# Sheet_1_2024-04-25.net
KiCad netlist of a schematic drawn in Altium Designer
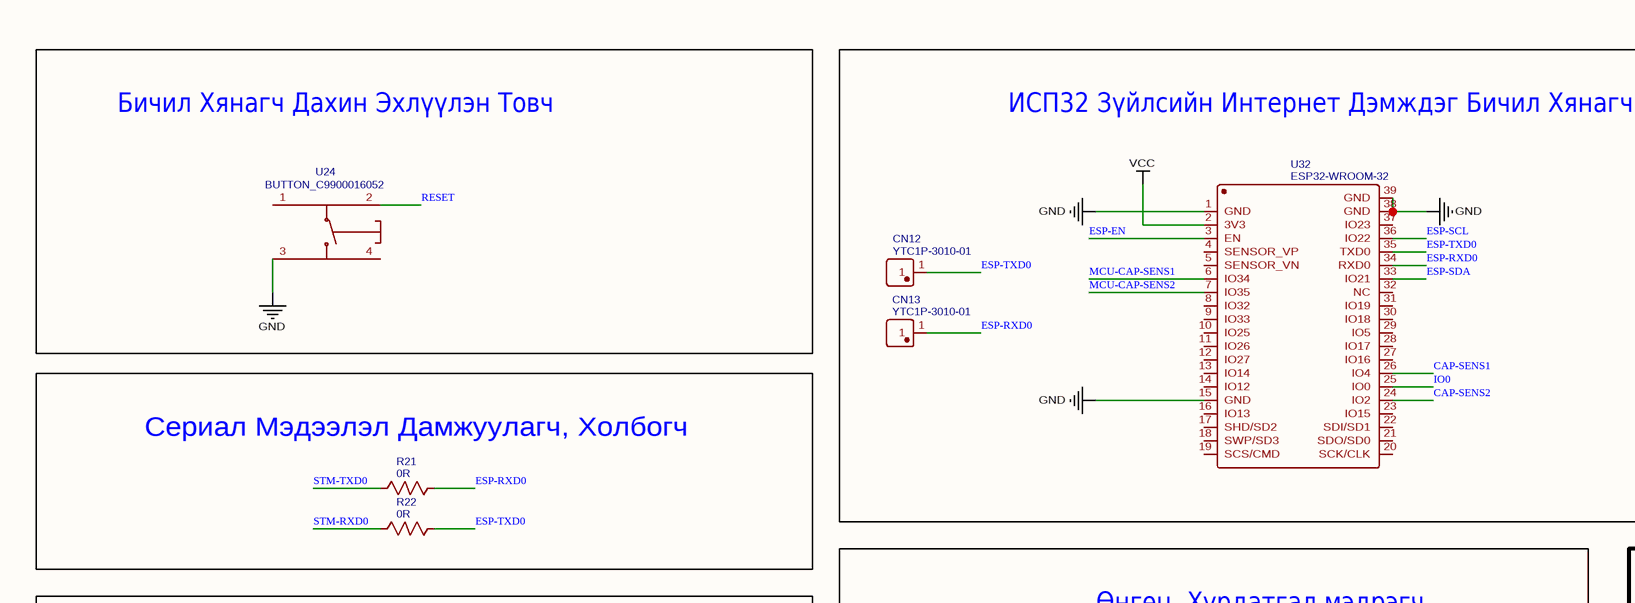
[diagram p0: Sheet_1_2024-04-25.schdoc, top left]
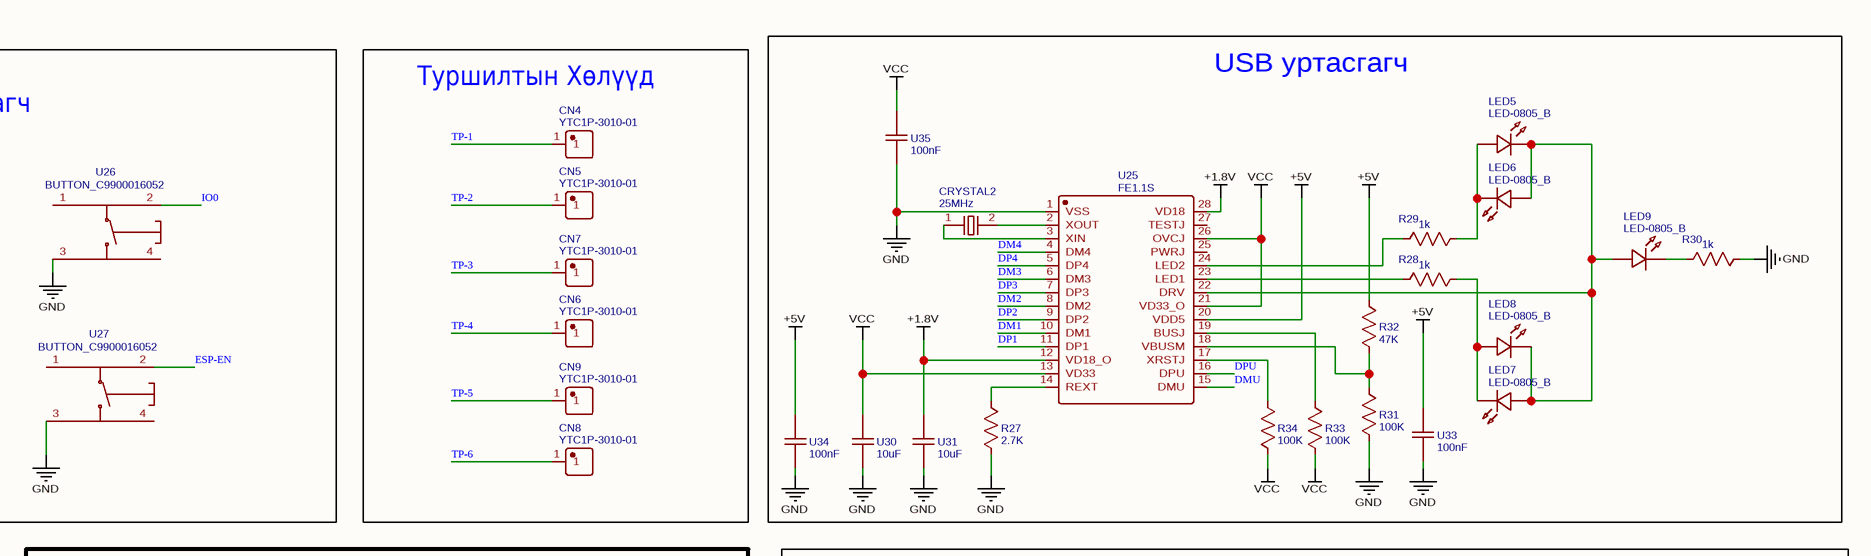
[diagram p1: Sheet_1_2024-04-25.schdoc, top right]
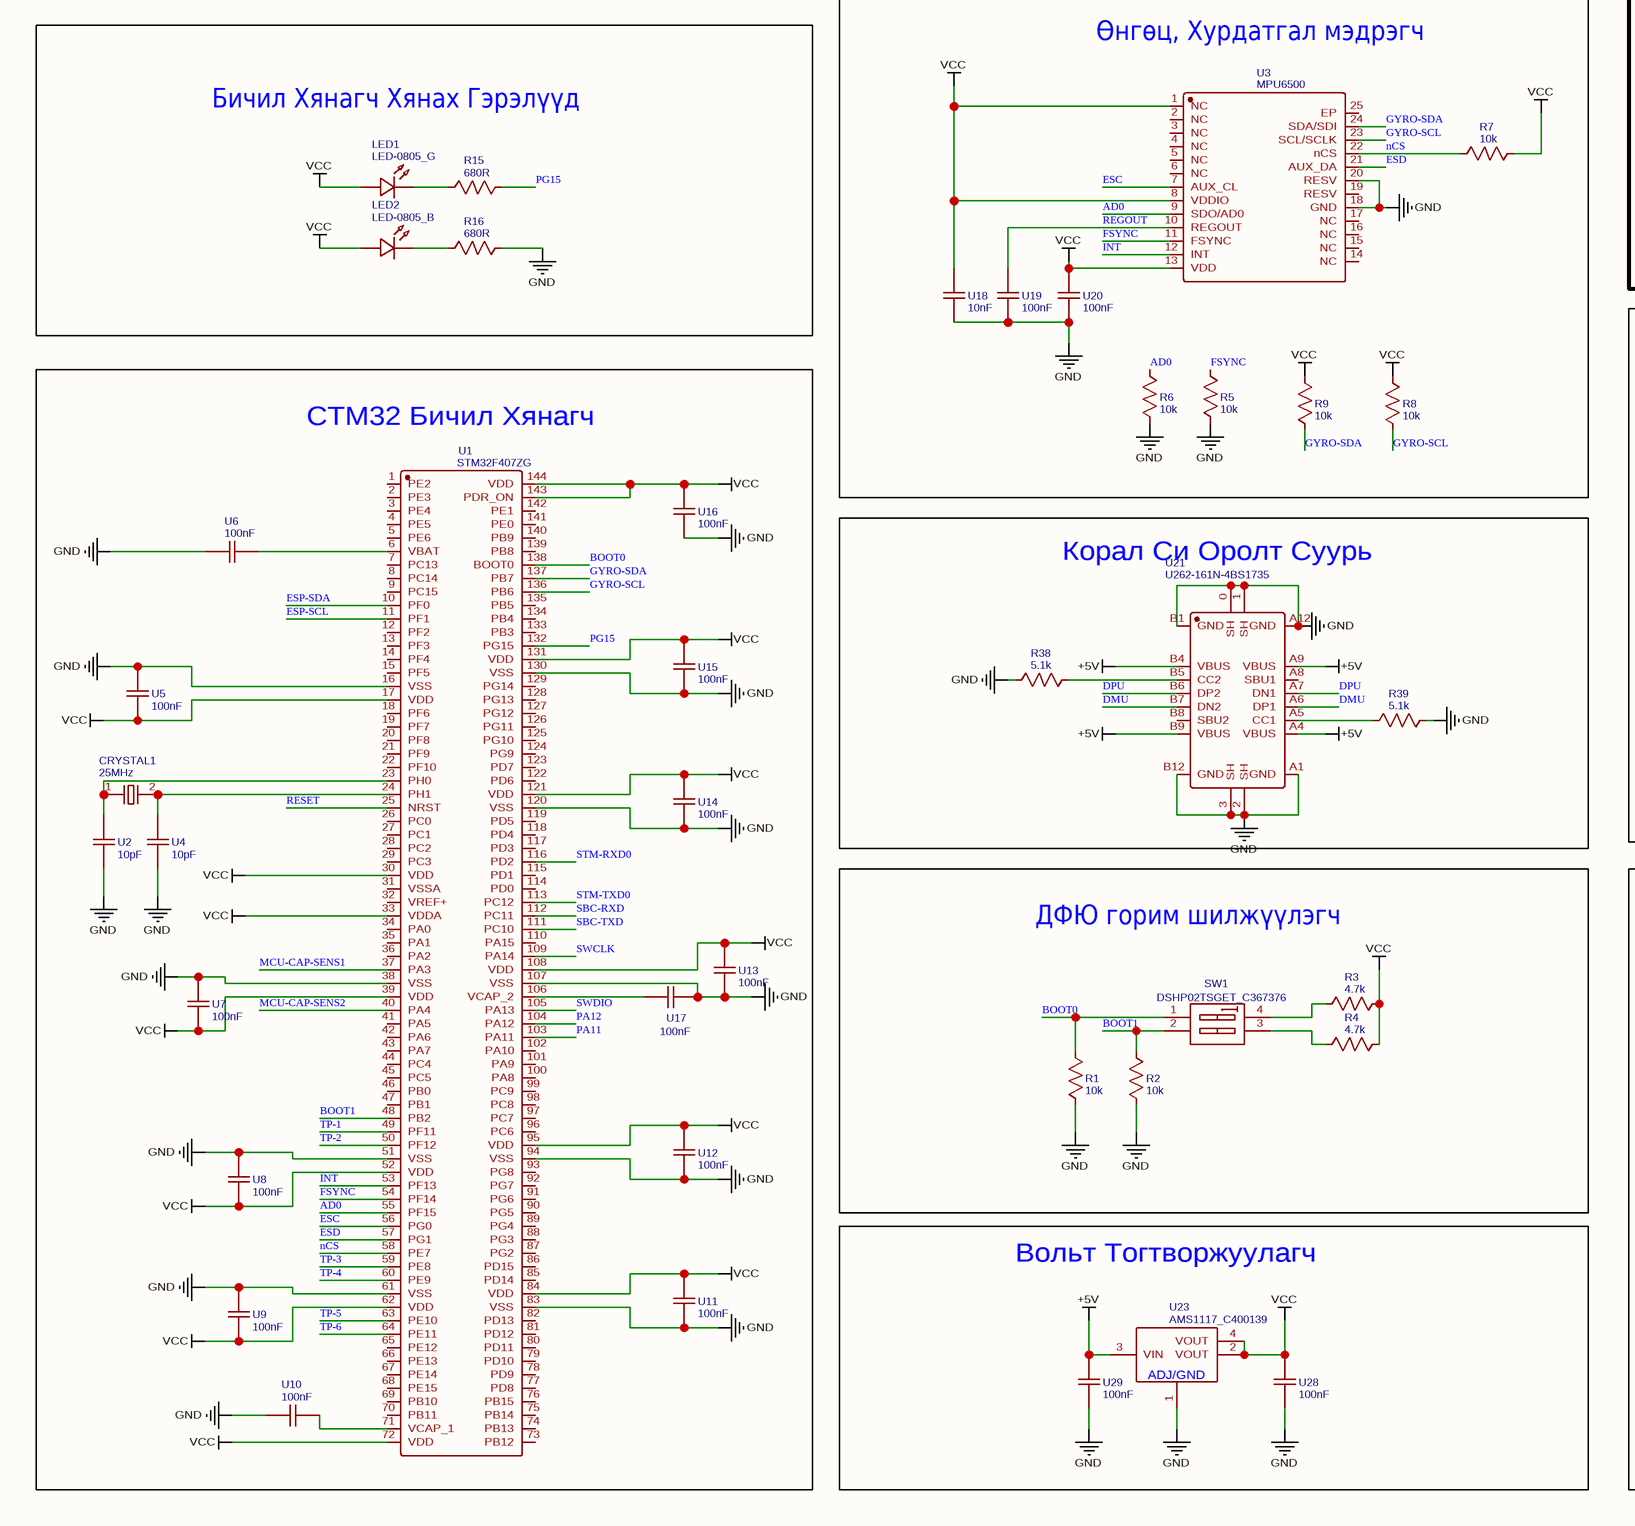
[diagram p2: Sheet_1_2024-04-25.schdoc, bottom left]
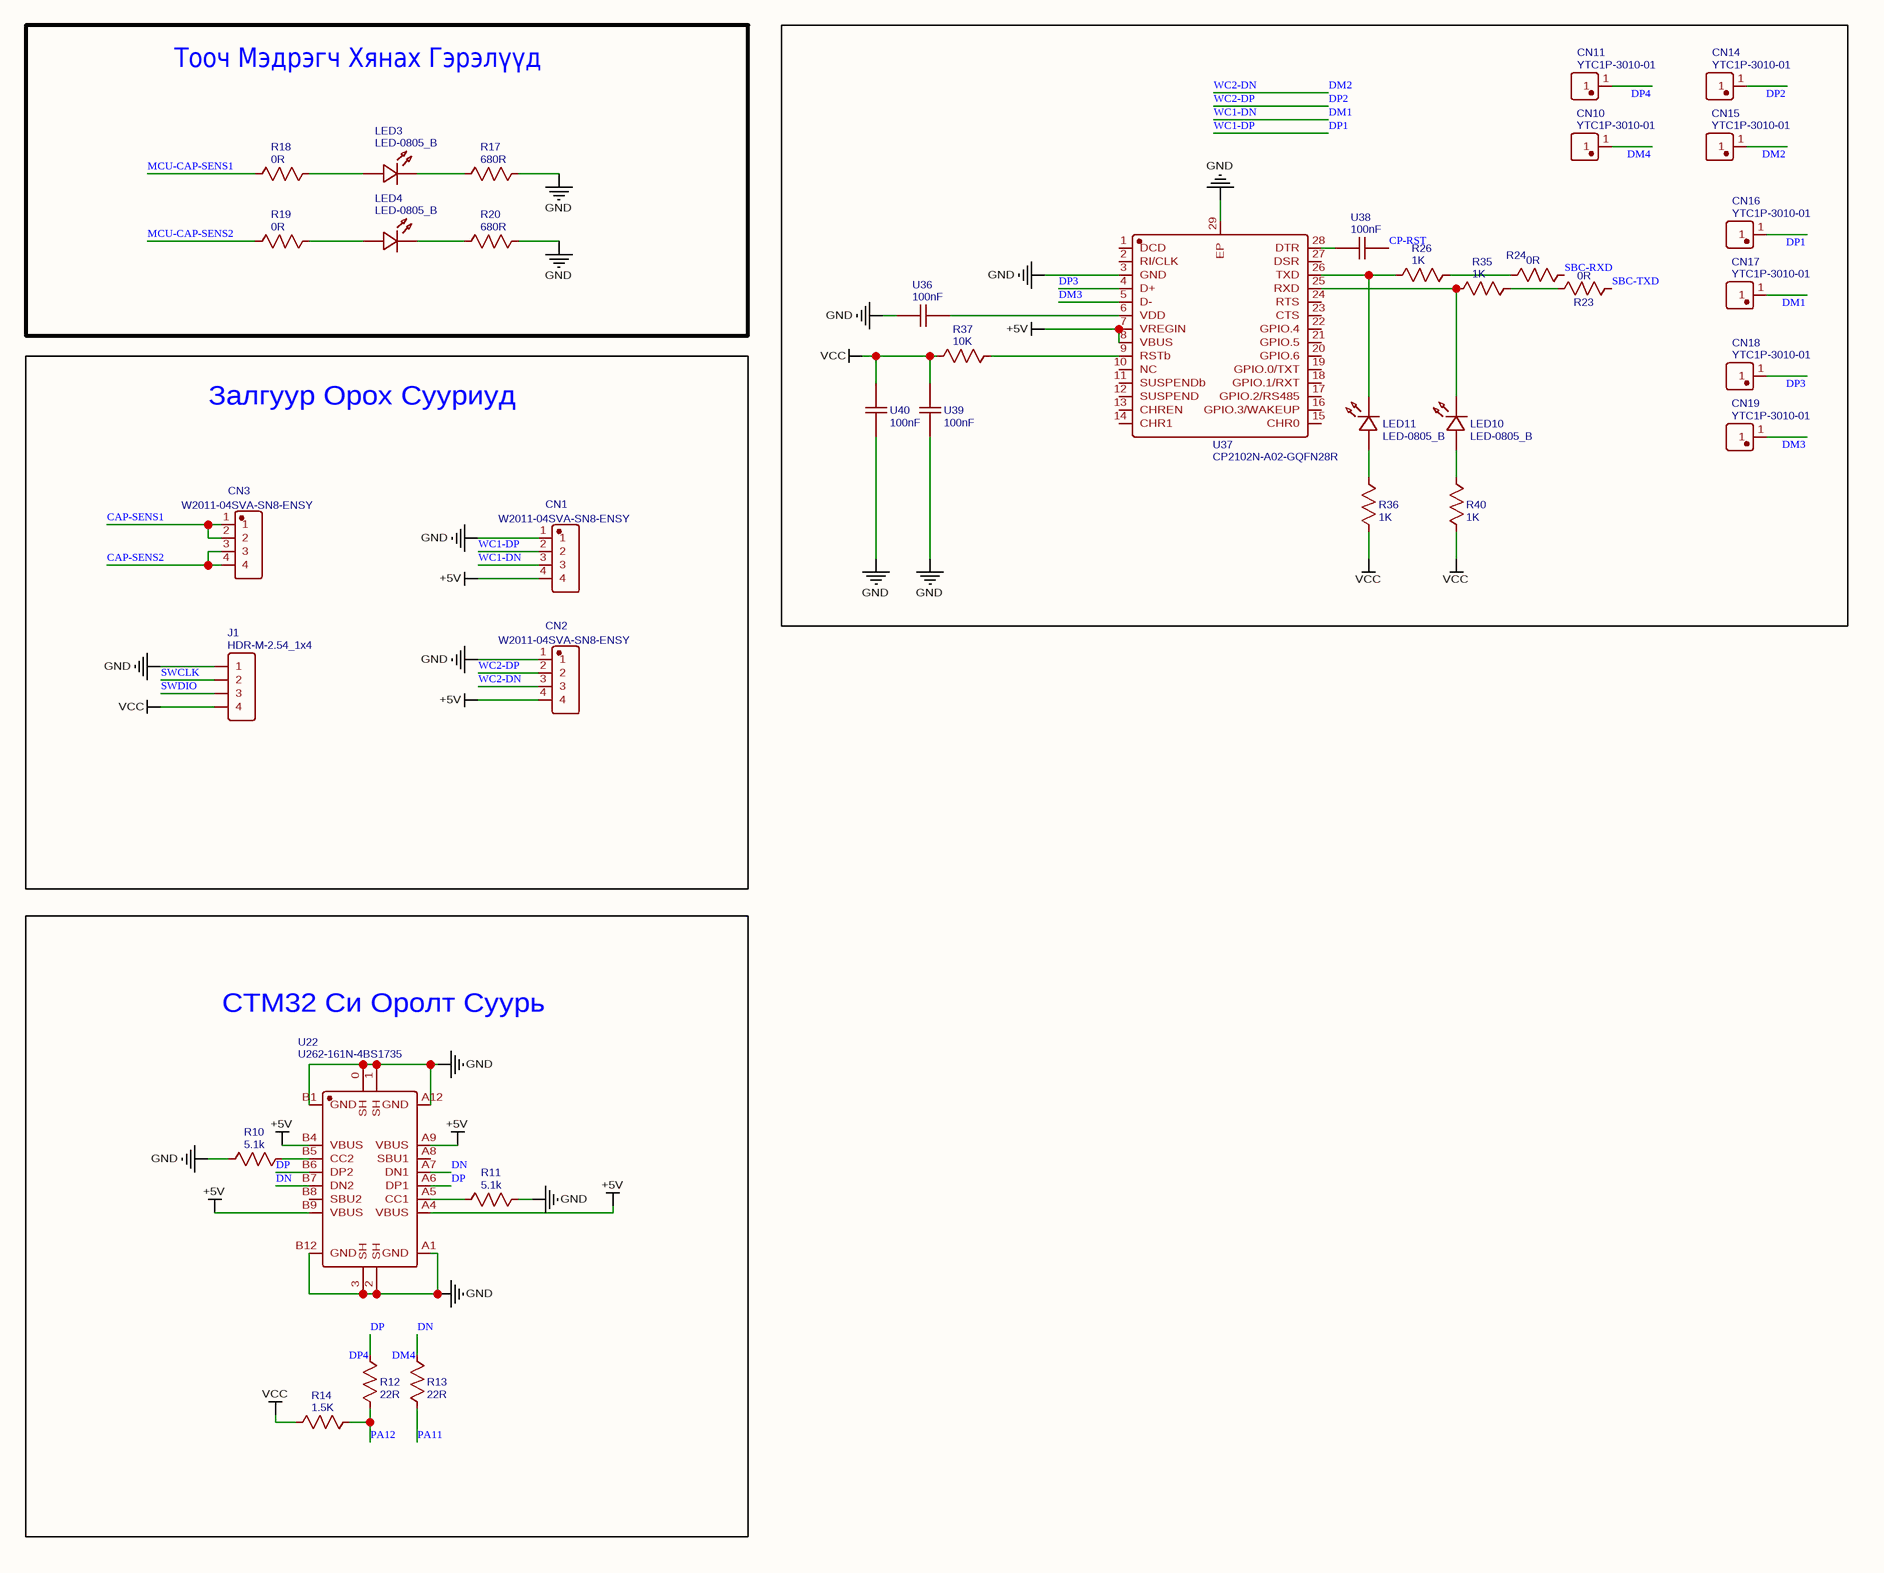
[diagram p3: Sheet_1_2024-04-25.schdoc, bottom right]

(export (version "E")
  (design (tool "Eeschema 10.0.6"))
  (components
    (comp (ref "CN1")
      (value "W2011-04SVA-SN8-ENSY")
      (fields (field (name "CONTRIBUTOR") "lcsc"))
      (libsource (lib "altium-import") (part "root_0_W2011-04SVA-SN8-ENSY_"))
    )
    (comp (ref "CN2")
      (value "W2011-04SVA-SN8-ENSY")
      (fields (field (name "CONTRIBUTOR") "lcsc"))
      (libsource (lib "altium-import") (part "root_0_W2011-04SVA-SN8-ENSY_"))
    )
    (comp (ref "CN3")
      (value "W2011-04SVA-SN8-ENSY")
      (fields (field (name "CONTRIBUTOR") "lcsc"))
      (libsource (lib "altium-import") (part "root_0_W2011-04SVA-SN8-ENSY_"))
    )
    (comp (ref "CN4")
      (value "YTC1P-3010-01")
      (fields (field (name "MANUFACTURER") "YIYUAN(怡远)") (field (name "CONTRIBUTOR") "lcsc"))
      (libsource (lib "altium-import") (part "root_0_YTC1P-3010-01_"))
    )
    (comp (ref "CN5")
      (value "YTC1P-3010-01")
      (fields (field (name "MANUFACTURER") "YIYUAN(怡远)") (field (name "CONTRIBUTOR") "lcsc"))
      (libsource (lib "altium-import") (part "root_0_YTC1P-3010-01_"))
    )
    (comp (ref "CN6")
      (value "YTC1P-3010-01")
      (fields (field (name "MANUFACTURER") "YIYUAN(怡远)") (field (name "CONTRIBUTOR") "lcsc"))
      (libsource (lib "altium-import") (part "root_0_YTC1P-3010-01_"))
    )
    (comp (ref "CN7")
      (value "YTC1P-3010-01")
      (fields (field (name "MANUFACTURER") "YIYUAN(怡远)") (field (name "CONTRIBUTOR") "lcsc"))
      (libsource (lib "altium-import") (part "root_0_YTC1P-3010-01_"))
    )
    (comp (ref "CN8")
      (value "YTC1P-3010-01")
      (fields (field (name "MANUFACTURER") "YIYUAN(怡远)") (field (name "CONTRIBUTOR") "lcsc"))
      (libsource (lib "altium-import") (part "root_0_YTC1P-3010-01_"))
    )
    (comp (ref "CN9")
      (value "YTC1P-3010-01")
      (fields (field (name "MANUFACTURER") "YIYUAN(怡远)") (field (name "CONTRIBUTOR") "lcsc"))
      (libsource (lib "altium-import") (part "root_0_YTC1P-3010-01_"))
    )
    (comp (ref "CN10")
      (value "YTC1P-3010-01")
      (fields (field (name "MANUFACTURER") "YIYUAN(怡远)") (field (name "CONTRIBUTOR") "lcsc"))
      (libsource (lib "altium-import") (part "root_2_YTC1P-3010-01_"))
    )
    (comp (ref "CN11")
      (value "YTC1P-3010-01")
      (fields (field (name "MANUFACTURER") "YIYUAN(怡远)") (field (name "CONTRIBUTOR") "lcsc"))
      (libsource (lib "altium-import") (part "root_2_YTC1P-3010-01_"))
    )
    (comp (ref "CN12")
      (value "YTC1P-3010-01")
      (fields (field (name "MANUFACTURER") "YIYUAN(怡远)") (field (name "CONTRIBUTOR") "lcsc"))
      (libsource (lib "altium-import") (part "root_2_YTC1P-3010-01_"))
    )
    (comp (ref "CN13")
      (value "YTC1P-3010-01")
      (fields (field (name "MANUFACTURER") "YIYUAN(怡远)") (field (name "CONTRIBUTOR") "lcsc"))
      (libsource (lib "altium-import") (part "root_2_YTC1P-3010-01_"))
    )
    (comp (ref "CN14")
      (value "YTC1P-3010-01")
      (fields (field (name "MANUFACTURER") "YIYUAN(怡远)") (field (name "CONTRIBUTOR") "lcsc"))
      (libsource (lib "altium-import") (part "root_2_YTC1P-3010-01_"))
    )
    (comp (ref "CN15")
      (value "YTC1P-3010-01")
      (fields (field (name "MANUFACTURER") "YIYUAN(怡远)") (field (name "CONTRIBUTOR") "lcsc"))
      (libsource (lib "altium-import") (part "root_2_YTC1P-3010-01_"))
    )
    (comp (ref "CN16")
      (value "YTC1P-3010-01")
      (fields (field (name "MANUFACTURER") "YIYUAN(怡远)") (field (name "CONTRIBUTOR") "lcsc"))
      (libsource (lib "altium-import") (part "root_2_YTC1P-3010-01_"))
    )
    (comp (ref "CN17")
      (value "YTC1P-3010-01")
      (fields (field (name "MANUFACTURER") "YIYUAN(怡远)") (field (name "CONTRIBUTOR") "lcsc"))
      (libsource (lib "altium-import") (part "root_2_YTC1P-3010-01_"))
    )
    (comp (ref "CN18")
      (value "YTC1P-3010-01")
      (fields (field (name "MANUFACTURER") "YIYUAN(怡远)") (field (name "CONTRIBUTOR") "lcsc"))
      (libsource (lib "altium-import") (part "root_2_YTC1P-3010-01_"))
    )
    (comp (ref "CN19")
      (value "YTC1P-3010-01")
      (fields (field (name "MANUFACTURER") "YIYUAN(怡远)") (field (name "CONTRIBUTOR") "lcsc"))
      (libsource (lib "altium-import") (part "root_2_YTC1P-3010-01_"))
    )
    (comp (ref "CRYSTAL1")
      (value "25MHz")
      (fields
        (field (name "MANUFACTURER") "HUAXIN(华昕)")
        (field (name "MANUFACTURER PART") "SD2012M00020001")
        (field (name "CONTRIBUTOR") "lcsc")
      )
      (libsource (lib "altium-import") (part "root_0_25MHz_"))
    )
    (comp (ref "CRYSTAL2")
      (value "25MHz")
      (fields
        (field (name "MANUFACTURER") "HUAXIN(华昕)")
        (field (name "MANUFACTURER PART") "SD2012M00020001")
        (field (name "CONTRIBUTOR") "lcsc")
      )
      (libsource (lib "altium-import") (part "root_0_25MHz_"))
    )
    (comp (ref "J1")
      (value "HDR-M-2.54_1x4")
      (fields (field (name "CONTRIBUTOR") "LCEDA_Lib"))
      (libsource (lib "altium-import") (part "root_0_HDR-M-2.54_1x4_"))
    )
    (comp (ref "LED1")
      (value "LED-0805_G")
      (fields
        (field (name "MANUFACTURER") "国星光电")
        (field (name "MANUFACTURER PART") "NCD0805G1")
        (field (name "CONTRIBUTOR") "LCEDA_Lib")
      )
      (libsource (lib "altium-import") (part "root_0_LED-0805_G_"))
    )
    (comp (ref "LED2")
      (value "LED-0805_B")
      (fields
        (field (name "MANUFACTURER") "方舟 ARKLED")
        (field (name "MANUFACTURER PART") "D-B080508B1-KS2")
        (field (name "CONTRIBUTOR") "LCEDA_Lib")
      )
      (libsource (lib "altium-import") (part "root_0_LED-0805_B_"))
    )
    (comp (ref "LED3")
      (value "LED-0805_B")
      (fields
        (field (name "MANUFACTURER") "方舟 ARKLED")
        (field (name "MANUFACTURER PART") "D-B080508B1-KS2")
        (field (name "CONTRIBUTOR") "LCEDA_Lib")
      )
      (libsource (lib "altium-import") (part "root_0_LED-0805_B_"))
    )
    (comp (ref "LED4")
      (value "LED-0805_B")
      (fields
        (field (name "MANUFACTURER") "方舟 ARKLED")
        (field (name "MANUFACTURER PART") "D-B080508B1-KS2")
        (field (name "CONTRIBUTOR") "LCEDA_Lib")
      )
      (libsource (lib "altium-import") (part "root_0_LED-0805_B_"))
    )
    (comp (ref "LED5")
      (value "LED-0805_B")
      (fields
        (field (name "MANUFACTURER") "方舟 ARKLED")
        (field (name "MANUFACTURER PART") "D-B080508B1-KS2")
        (field (name "CONTRIBUTOR") "LCEDA_Lib")
      )
      (libsource (lib "altium-import") (part "root_0_LED-0805_B_"))
    )
    (comp (ref "LED6")
      (value "LED-0805_B")
      (fields
        (field (name "MANUFACTURER") "方舟 ARKLED")
        (field (name "MANUFACTURER PART") "D-B080508B1-KS2")
        (field (name "CONTRIBUTOR") "LCEDA_Lib")
      )
      (libsource (lib "altium-import") (part "root_2_LED-0805_B_"))
    )
    (comp (ref "LED7")
      (value "LED-0805_B")
      (fields
        (field (name "MANUFACTURER") "方舟 ARKLED")
        (field (name "MANUFACTURER PART") "D-B080508B1-KS2")
        (field (name "CONTRIBUTOR") "LCEDA_Lib")
      )
      (libsource (lib "altium-import") (part "root_2_LED-0805_B_"))
    )
    (comp (ref "LED8")
      (value "LED-0805_B")
      (fields
        (field (name "MANUFACTURER") "方舟 ARKLED")
        (field (name "MANUFACTURER PART") "D-B080508B1-KS2")
        (field (name "CONTRIBUTOR") "LCEDA_Lib")
      )
      (libsource (lib "altium-import") (part "root_0_LED-0805_B_"))
    )
    (comp (ref "LED9")
      (value "LED-0805_B")
      (fields
        (field (name "MANUFACTURER") "方舟 ARKLED")
        (field (name "MANUFACTURER PART") "D-B080508B1-KS2")
        (field (name "CONTRIBUTOR") "LCEDA_Lib")
      )
      (libsource (lib "altium-import") (part "root_0_LED-0805_B_"))
    )
    (comp (ref "LED10")
      (value "LED-0805_B")
      (fields
        (field (name "MANUFACTURER") "方舟 ARKLED")
        (field (name "MANUFACTURER PART") "D-B080508B1-KS2")
        (field (name "CONTRIBUTOR") "LCEDA_Lib")
      )
      (libsource (lib "altium-import") (part "root_1_LED-0805_B_"))
    )
    (comp (ref "LED11")
      (value "LED-0805_B")
      (fields
        (field (name "MANUFACTURER") "方舟 ARKLED")
        (field (name "MANUFACTURER PART") "D-B080508B1-KS2")
        (field (name "CONTRIBUTOR") "LCEDA_Lib")
      )
      (libsource (lib "altium-import") (part "root_1_LED-0805_B_"))
    )
    (comp (ref "R1")
      (value "10k")
      (fields (field (name "CONTRIBUTOR") "LCEDA_Lib"))
      (libsource (lib "altium-import") (part "root_1_10k_"))
    )
    (comp (ref "R2")
      (value "10k")
      (fields (field (name "CONTRIBUTOR") "LCEDA_Lib"))
      (libsource (lib "altium-import") (part "root_1_10k_"))
    )
    (comp (ref "R3")
      (value "4.7k")
      (fields (field (name "CONTRIBUTOR") "LCEDA_Lib"))
      (libsource (lib "altium-import") (part "root_2_4.7k_"))
    )
    (comp (ref "R4")
      (value "4.7k")
      (fields (field (name "CONTRIBUTOR") "LCEDA_Lib"))
      (libsource (lib "altium-import") (part "root_2_4.7k_"))
    )
    (comp (ref "R5")
      (value "10k")
      (fields (field (name "CONTRIBUTOR") "LCEDA_Lib"))
      (libsource (lib "altium-import") (part "root_1_10k_"))
    )
    (comp (ref "R6")
      (value "10k")
      (fields (field (name "CONTRIBUTOR") "LCEDA_Lib"))
      (libsource (lib "altium-import") (part "root_1_10k_"))
    )
    (comp (ref "R7")
      (value "10k")
      (fields (field (name "CONTRIBUTOR") "LCEDA_Lib"))
      (libsource (lib "altium-import") (part "root_2_10k_"))
    )
    (comp (ref "R8")
      (value "10k")
      (fields (field (name "CONTRIBUTOR") "LCEDA_Lib"))
      (libsource (lib "altium-import") (part "root_3_10k_"))
    )
    (comp (ref "R9")
      (value "10k")
      (fields (field (name "CONTRIBUTOR") "LCEDA_Lib"))
      (libsource (lib "altium-import") (part "root_3_10k_"))
    )
    (comp (ref "R10")
      (value "5.1k")
      (fields (field (name "CONTRIBUTOR") "LCEDA_Lib"))
      (libsource (lib "altium-import") (part "root_2_5.1k_"))
    )
    (comp (ref "R11")
      (value "5.1k")
      (fields (field (name "CONTRIBUTOR") "LCEDA_Lib"))
      (libsource (lib "altium-import") (part "root_2_5.1k_"))
    )
    (comp (ref "R12")
      (value "22R")
      (fields (field (name "CONTRIBUTOR") "LCEDA_Lib"))
      (libsource (lib "altium-import") (part "root_3_22R_"))
    )
    (comp (ref "R13")
      (value "22R")
      (fields (field (name "CONTRIBUTOR") "LCEDA_Lib"))
      (libsource (lib "altium-import") (part "root_3_22R_"))
    )
    (comp (ref "R14")
      (value "1.5K")
      (fields (field (name "CONTRIBUTOR") "LCEDA_Lib"))
      (libsource (lib "altium-import") (part "root_0_1.5K_"))
    )
    (comp (ref "R15")
      (value "680R")
      (fields (field (name "CONTRIBUTOR") "LCEDA_Lib"))
      (libsource (lib "altium-import") (part "root_0_680R_"))
    )
    (comp (ref "R16")
      (value "680R")
      (fields (field (name "CONTRIBUTOR") "LCEDA_Lib"))
      (libsource (lib "altium-import") (part "root_0_680R_"))
    )
    (comp (ref "R17")
      (value "680R")
      (fields (field (name "CONTRIBUTOR") "LCEDA_Lib"))
      (libsource (lib "altium-import") (part "root_0_680R_"))
    )
    (comp (ref "R18")
      (value "0R")
      (fields (field (name "CONTRIBUTOR") "LCEDA_Lib"))
      (libsource (lib "altium-import") (part "root_0_0R_"))
    )
    (comp (ref "R19")
      (value "0R")
      (fields (field (name "CONTRIBUTOR") "LCEDA_Lib"))
      (libsource (lib "altium-import") (part "root_0_0R_"))
    )
    (comp (ref "R20")
      (value "680R")
      (fields (field (name "CONTRIBUTOR") "LCEDA_Lib"))
      (libsource (lib "altium-import") (part "root_0_680R_"))
    )
    (comp (ref "R21")
      (value "0R")
      (fields (field (name "CONTRIBUTOR") "LCEDA_Lib"))
      (libsource (lib "altium-import") (part "root_0_0R_"))
    )
    (comp (ref "R22")
      (value "0R")
      (fields (field (name "CONTRIBUTOR") "LCEDA_Lib"))
      (libsource (lib "altium-import") (part "root_0_0R_"))
    )
    (comp (ref "R23")
      (value "0R")
      (fields (field (name "CONTRIBUTOR") "LCEDA_Lib"))
      (libsource (lib "altium-import") (part "root_0_0R_"))
    )
    (comp (ref "R24")
      (value "0R")
      (fields (field (name "CONTRIBUTOR") "LCEDA_Lib"))
      (libsource (lib "altium-import") (part "root_0_0R_"))
    )
    (comp (ref "R26")
      (value "1K")
      (fields (field (name "CONTRIBUTOR") "LCEDA_Lib"))
      (libsource (lib "altium-import") (part "root_2_1K_"))
    )
    (comp (ref "R27")
      (value "2.7K")
      (fields (field (name "CONTRIBUTOR") "LCEDA_Lib"))
      (libsource (lib "altium-import") (part "root_1_2.7K_"))
    )
    (comp (ref "R28")
      (value "1k")
      (fields (field (name "CONTRIBUTOR") "LCEDA_Lib"))
      (libsource (lib "altium-import") (part "root_0_1k_"))
    )
    (comp (ref "R29")
      (value "1k")
      (fields (field (name "CONTRIBUTOR") "LCEDA_Lib"))
      (libsource (lib "altium-import") (part "root_0_1k_"))
    )
    (comp (ref "R30")
      (value "1k")
      (fields (field (name "CONTRIBUTOR") "LCEDA_Lib"))
      (libsource (lib "altium-import") (part "root_0_1k_"))
    )
    (comp (ref "R31")
      (value "100K")
      (fields (field (name "CONTRIBUTOR") "LCEDA_Lib"))
      (libsource (lib "altium-import") (part "root_1_100K_"))
    )
    (comp (ref "R32")
      (value "47K")
      (fields (field (name "CONTRIBUTOR") "LCEDA_Lib"))
      (libsource (lib "altium-import") (part "root_1_47K_"))
    )
    (comp (ref "R33")
      (value "100K")
      (fields (field (name "CONTRIBUTOR") "LCEDA_Lib"))
      (libsource (lib "altium-import") (part "root_3_100K_"))
    )
    (comp (ref "R34")
      (value "100K")
      (fields (field (name "CONTRIBUTOR") "LCEDA_Lib"))
      (libsource (lib "altium-import") (part "root_3_100K_"))
    )
    (comp (ref "R35")
      (value "1K")
      (fields (field (name "CONTRIBUTOR") "LCEDA_Lib"))
      (libsource (lib "altium-import") (part "root_2_1K_"))
    )
    (comp (ref "R36")
      (value "1K")
      (fields (field (name "CONTRIBUTOR") "LCEDA_Lib"))
      (libsource (lib "altium-import") (part "root_1_1K_"))
    )
    (comp (ref "R37")
      (value "10K")
      (fields (field (name "CONTRIBUTOR") "LCEDA_Lib"))
      (libsource (lib "altium-import") (part "root_2_10K_"))
    )
    (comp (ref "R38")
      (value "5.1k")
      (fields (field (name "CONTRIBUTOR") "LCEDA_Lib"))
      (libsource (lib "altium-import") (part "root_2_5.1k_"))
    )
    (comp (ref "R39")
      (value "5.1k")
      (fields (field (name "CONTRIBUTOR") "LCEDA_Lib"))
      (libsource (lib "altium-import") (part "root_2_5.1k_"))
    )
    (comp (ref "R40")
      (value "1K")
      (fields (field (name "CONTRIBUTOR") "LCEDA_Lib"))
      (libsource (lib "altium-import") (part "root_1_1K_"))
    )
    (comp (ref "SW1")
      (value "DSHP02TSGET_C367376")
      (fields
        (field (name "MANUFACTURER") "YE")
        (field (name "MANUFACTURER PART") "DSHP02TSGER")
        (field (name "CONTRIBUTOR") "LCSC")
      )
      (libsource (lib "altium-import") (part "root_0_DSHP02TSGET_C367376_"))
    )
    (comp (ref "U1")
      (value "STM32F407ZG")
      (fields (field (name "CONTRIBUTOR") "LCSC"))
      (libsource (lib "altium-import") (part "root_0_STM32F407ZG_"))
    )
    (comp (ref "U2")
      (value "10pF")
      (fields
        (field (name "MANUFACTURER") "Walsin(华新科)")
        (field (name "MANUFACTURER PART") "0805N220J500CT-C")
        (field (name "CONTRIBUTOR") "lcsc")
      )
      (libsource (lib "altium-import") (part "root_1_10pF_"))
    )
    (comp (ref "U3")
      (value "MPU6500")
      (fields
        (field (name "MANUFACTURER") "TDK InvenSense(应美盛)")
        (field (name "MANUFACTURER PART") "MPU-6500")
      )
      (libsource (lib "altium-import") (part "root_0_MPU6500_"))
    )
    (comp (ref "U4")
      (value "10pF")
      (fields
        (field (name "MANUFACTURER") "Walsin(华新科)")
        (field (name "MANUFACTURER PART") "0805N220J500CT-C")
        (field (name "CONTRIBUTOR") "lcsc")
      )
      (libsource (lib "altium-import") (part "root_1_10pF_"))
    )
    (comp (ref "U5")
      (value "100nF")
      (fields
        (field (name "MANUFACTURER") "Walsin(华新科)")
        (field (name "MANUFACTURER PART") "0805N220J500CT-C")
        (field (name "CONTRIBUTOR") "lcsc")
      )
      (libsource (lib "altium-import") (part "root_3_100nF_"))
    )
    (comp (ref "U6")
      (value "100nF")
      (fields
        (field (name "MANUFACTURER") "Walsin(华新科)")
        (field (name "MANUFACTURER PART") "0805N220J500CT-C")
        (field (name "CONTRIBUTOR") "lcsc")
      )
      (libsource (lib "altium-import") (part "root_0_100nF_"))
    )
    (comp (ref "U7")
      (value "100nF")
      (fields
        (field (name "MANUFACTURER") "Walsin(华新科)")
        (field (name "MANUFACTURER PART") "0805N220J500CT-C")
        (field (name "CONTRIBUTOR") "lcsc")
      )
      (libsource (lib "altium-import") (part "root_3_100nF_"))
    )
    (comp (ref "U8")
      (value "100nF")
      (fields
        (field (name "MANUFACTURER") "Walsin(华新科)")
        (field (name "MANUFACTURER PART") "0805N220J500CT-C")
        (field (name "CONTRIBUTOR") "lcsc")
      )
      (libsource (lib "altium-import") (part "root_3_100nF_"))
    )
    (comp (ref "U9")
      (value "100nF")
      (fields
        (field (name "MANUFACTURER") "Walsin(华新科)")
        (field (name "MANUFACTURER PART") "0805N220J500CT-C")
        (field (name "CONTRIBUTOR") "lcsc")
      )
      (libsource (lib "altium-import") (part "root_3_100nF_"))
    )
    (comp (ref "U10")
      (value "100nF")
      (fields
        (field (name "MANUFACTURER") "Walsin(华新科)")
        (field (name "MANUFACTURER PART") "0805N220J500CT-C")
        (field (name "CONTRIBUTOR") "lcsc")
      )
      (libsource (lib "altium-import") (part "root_0_100nF_"))
    )
    (comp (ref "U11")
      (value "100nF")
      (fields
        (field (name "MANUFACTURER") "Walsin(华新科)")
        (field (name "MANUFACTURER PART") "0805N220J500CT-C")
        (field (name "CONTRIBUTOR") "lcsc")
      )
      (libsource (lib "altium-import") (part "root_1_100nF_"))
    )
    (comp (ref "U12")
      (value "100nF")
      (fields
        (field (name "MANUFACTURER") "Walsin(华新科)")
        (field (name "MANUFACTURER PART") "0805N220J500CT-C")
        (field (name "CONTRIBUTOR") "lcsc")
      )
      (libsource (lib "altium-import") (part "root_1_100nF_"))
    )
    (comp (ref "U13")
      (value "100nF")
      (fields
        (field (name "MANUFACTURER") "Walsin(华新科)")
        (field (name "MANUFACTURER PART") "0805N220J500CT-C")
        (field (name "CONTRIBUTOR") "lcsc")
      )
      (libsource (lib "altium-import") (part "root_1_100nF_"))
    )
    (comp (ref "U14")
      (value "100nF")
      (fields
        (field (name "MANUFACTURER") "Walsin(华新科)")
        (field (name "MANUFACTURER PART") "0805N220J500CT-C")
        (field (name "CONTRIBUTOR") "lcsc")
      )
      (libsource (lib "altium-import") (part "root_1_100nF_"))
    )
    (comp (ref "U15")
      (value "100nF")
      (fields
        (field (name "MANUFACTURER") "Walsin(华新科)")
        (field (name "MANUFACTURER PART") "0805N220J500CT-C")
        (field (name "CONTRIBUTOR") "lcsc")
      )
      (libsource (lib "altium-import") (part "root_1_100nF_"))
    )
    (comp (ref "U16")
      (value "100nF")
      (fields
        (field (name "MANUFACTURER") "Walsin(华新科)")
        (field (name "MANUFACTURER PART") "0805N220J500CT-C")
        (field (name "CONTRIBUTOR") "lcsc")
      )
      (libsource (lib "altium-import") (part "root_1_100nF_"))
    )
    (comp (ref "U17")
      (value "100nF")
      (fields
        (field (name "MANUFACTURER") "Walsin(华新科)")
        (field (name "MANUFACTURER PART") "0805N220J500CT-C")
        (field (name "CONTRIBUTOR") "lcsc")
      )
      (libsource (lib "altium-import") (part "root_2_100nF_"))
    )
    (comp (ref "U18")
      (value "10nF")
      (fields
        (field (name "MANUFACTURER") "Walsin(华新科)")
        (field (name "MANUFACTURER PART") "0805N220J500CT-C")
        (field (name "CONTRIBUTOR") "lcsc")
      )
      (libsource (lib "altium-import") (part "root_3_10nF_"))
    )
    (comp (ref "U19")
      (value "100nF")
      (fields
        (field (name "MANUFACTURER") "Walsin(华新科)")
        (field (name "MANUFACTURER PART") "0805N220J500CT-C")
        (field (name "CONTRIBUTOR") "lcsc")
      )
      (libsource (lib "altium-import") (part "root_3_100nF_"))
    )
    (comp (ref "U20")
      (value "100nF")
      (fields
        (field (name "MANUFACTURER") "Walsin(华新科)")
        (field (name "MANUFACTURER PART") "0805N220J500CT-C")
        (field (name "CONTRIBUTOR") "lcsc")
      )
      (libsource (lib "altium-import") (part "root_3_100nF_"))
    )
    (comp (ref "U21")
      (value "U262-161N-4BS1735")
      (fields (field (name "MANUFACTURER") "XKB Connectivity(中国星坤)") (field (name "CONTRIBUTOR") "lcsc"))
      (libsource (lib "altium-import") (part "root_0_U262-161N-4BS1735_"))
    )
    (comp (ref "U22")
      (value "U262-161N-4BS1735")
      (fields (field (name "MANUFACTURER") "XKB Connectivity(中国星坤)") (field (name "CONTRIBUTOR") "lcsc"))
      (libsource (lib "altium-import") (part "root_0_U262-161N-4BS1735_"))
    )
    (comp (ref "U23")
      (value "AMS1117_C400139")
      (fields
        (field (name "MANUFACTURER") "UNI-SEMI(宇力半导体)")
        (field (name "MANUFACTURER PART") "AMS1117-T33")
        (field (name "CONTRIBUTOR") "LCSC")
      )
      (libsource (lib "altium-import") (part "root_0_AMS1117_C400139_"))
    )
    (comp (ref "U24")
      (value "BUTTON_C9900016052")
      (fields (field (name "MANUFACTURER PART") "button") (field (name "CONTRIBUTOR") "lcsc"))
      (libsource (lib "altium-import") (part "root_0_BUTTON_C9900016052_"))
    )
    (comp (ref "U25")
      (value "FE1.1S")
      (fields (field (name "MANUFACTURER") "TERMINUS") (field (name "MANUFACTURER PART") "FE1.1S-BSOP28BCN"))
      (libsource (lib "altium-import") (part "root_0_FE1.1S_"))
    )
    (comp (ref "U26")
      (value "BUTTON_C9900016052")
      (fields (field (name "MANUFACTURER PART") "button") (field (name "CONTRIBUTOR") "lcsc"))
      (libsource (lib "altium-import") (part "root_0_BUTTON_C9900016052_"))
    )
    (comp (ref "U27")
      (value "BUTTON_C9900016052")
      (fields (field (name "MANUFACTURER PART") "button") (field (name "CONTRIBUTOR") "lcsc"))
      (libsource (lib "altium-import") (part "root_0_BUTTON_C9900016052_"))
    )
    (comp (ref "U28")
      (value "100nF")
      (fields
        (field (name "MANUFACTURER") "Walsin(华新科)")
        (field (name "MANUFACTURER PART") "0805N220J500CT-C")
        (field (name "CONTRIBUTOR") "lcsc")
      )
      (libsource (lib "altium-import") (part "root_3_100nF_"))
    )
    (comp (ref "U29")
      (value "100nF")
      (fields
        (field (name "MANUFACTURER") "Walsin(华新科)")
        (field (name "MANUFACTURER PART") "0805N220J500CT-C")
        (field (name "CONTRIBUTOR") "lcsc")
      )
      (libsource (lib "altium-import") (part "root_3_100nF_"))
    )
    (comp (ref "U30")
      (value "10uF")
      (fields
        (field (name "MANUFACTURER") "Walsin(华新科)")
        (field (name "MANUFACTURER PART") "0805N220J500CT-C")
        (field (name "CONTRIBUTOR") "lcsc")
      )
      (libsource (lib "altium-import") (part "root_3_10uF_"))
    )
    (comp (ref "U31")
      (value "10uF")
      (fields
        (field (name "MANUFACTURER") "Walsin(华新科)")
        (field (name "MANUFACTURER PART") "0805N220J500CT-C")
        (field (name "CONTRIBUTOR") "lcsc")
      )
      (libsource (lib "altium-import") (part "root_3_10uF_"))
    )
    (comp (ref "U32")
      (value "ESP32-WROOM-32")
      (fields
        (field (name "MANUFACTURER") "ESPRESSIF(乐鑫)")
        (field (name "MANUFACTURER PART") "ESP32-WROOM-32-N4")
        (field (name "CONTRIBUTOR") "LCSC")
      )
      (libsource (lib "altium-import") (part "root_0_ESP32-WROOM-32_"))
    )
    (comp (ref "U33")
      (value "100nF")
      (fields
        (field (name "MANUFACTURER") "Walsin(华新科)")
        (field (name "MANUFACTURER PART") "0805N220J500CT-C")
        (field (name "CONTRIBUTOR") "lcsc")
      )
      (libsource (lib "altium-import") (part "root_3_100nF_"))
    )
    (comp (ref "U34")
      (value "100nF")
      (fields
        (field (name "MANUFACTURER") "Walsin(华新科)")
        (field (name "MANUFACTURER PART") "0805N220J500CT-C")
        (field (name "CONTRIBUTOR") "lcsc")
      )
      (libsource (lib "altium-import") (part "root_3_100nF_"))
    )
    (comp (ref "U35")
      (value "100nF")
      (fields
        (field (name "MANUFACTURER") "Walsin(华新科)")
        (field (name "MANUFACTURER PART") "0805N220J500CT-C")
        (field (name "CONTRIBUTOR") "lcsc")
      )
      (libsource (lib "altium-import") (part "root_3_100nF_"))
    )
    (comp (ref "U36")
      (value "100nF")
      (fields
        (field (name "MANUFACTURER") "Walsin(华新科)")
        (field (name "MANUFACTURER PART") "0805N220J500CT-C")
        (field (name "CONTRIBUTOR") "lcsc")
      )
      (libsource (lib "altium-import") (part "root_0_100nF_"))
    )
    (comp (ref "U37")
      (value "CP2102N-A02-GQFN28R")
      (fields (field (name "MANUFACTURER") "SKYWORKS/SILICON LABS(芯科)") (field (name "CONTRIBUTOR") "LCSC"))
      (libsource (lib "altium-import") (part "root_0_CP2102N-A02-GQFN28R_"))
    )
    (comp (ref "U38")
      (value "100nF")
      (fields
        (field (name "MANUFACTURER") "Walsin(华新科)")
        (field (name "MANUFACTURER PART") "0805N220J500CT-C")
        (field (name "CONTRIBUTOR") "lcsc")
      )
      (libsource (lib "altium-import") (part "root_0_100nF_"))
    )
    (comp (ref "U39")
      (value "100nF")
      (fields
        (field (name "MANUFACTURER") "Walsin(华新科)")
        (field (name "MANUFACTURER PART") "0805N220J500CT-C")
        (field (name "CONTRIBUTOR") "lcsc")
      )
      (libsource (lib "altium-import") (part "root_1_100nF_"))
    )
    (comp (ref "U40")
      (value "100nF")
      (fields
        (field (name "MANUFACTURER") "Walsin(华新科)")
        (field (name "MANUFACTURER PART") "0805N220J500CT-C")
        (field (name "CONTRIBUTOR") "lcsc")
      )
      (libsource (lib "altium-import") (part "root_1_100nF_"))
    )
  )
  (nets
    (net (code "1") (name "+1.8V") (class "Default")
      (node (ref "U25") (pin "12") (pinfunction "VD18_O_12") (pintype "passive"))
      (node (ref "U25") (pin "28") (pinfunction "VD18_28") (pintype "passive"))
      (node (ref "U31") (pin "1") (pinfunction "1_1") (pintype "passive"))
    )
    (net (code "2") (name "+5V") (class "Default")
      (node (ref "CN1") (pin "4") (pinfunction "4_4") (pintype "passive"))
      (node (ref "CN2") (pin "4") (pinfunction "4_4") (pintype "passive"))
      (node (ref "R32") (pin "2") (pinfunction "2_2") (pintype "passive"))
      (node (ref "U21") (pin "A4") (pinfunction "VBUS_A4") (pintype "passive"))
      (node (ref "U21") (pin "A9") (pinfunction "VBUS_A9") (pintype "passive"))
      (node (ref "U21") (pin "B4") (pinfunction "VBUS_B4") (pintype "passive"))
      (node (ref "U21") (pin "B9") (pinfunction "VBUS_B9") (pintype "passive"))
      (node (ref "U22") (pin "A4") (pinfunction "VBUS_A4") (pintype "passive"))
      (node (ref "U22") (pin "A9") (pinfunction "VBUS_A9") (pintype "passive"))
      (node (ref "U22") (pin "B4") (pinfunction "VBUS_B4") (pintype "passive"))
      (node (ref "U22") (pin "B9") (pinfunction "VBUS_B9") (pintype "passive"))
      (node (ref "U23") (pin "3") (pinfunction "VIN_3") (pintype "passive"))
      (node (ref "U25") (pin "20") (pinfunction "VDD5_20") (pintype "passive"))
      (node (ref "U29") (pin "1") (pinfunction "1_1") (pintype "passive"))
      (node (ref "U33") (pin "1") (pinfunction "1_1") (pintype "passive"))
      (node (ref "U34") (pin "1") (pinfunction "1_1") (pintype "passive"))
      (node (ref "U37") (pin "7") (pinfunction "VREGIN_7") (pintype "passive"))
      (node (ref "U37") (pin "8") (pinfunction "VBUS_8") (pintype "passive"))
    )
    (net (code "3") (name "/AD0") (class "Default")
      (node (ref "R6") (pin "2") (pinfunction "2_2") (pintype "passive"))
      (node (ref "U1") (pin "55") (pinfunction "PF15_55") (pintype "passive"))
      (node (ref "U3") (pin "9") (pinfunction "SDO/AD0_9") (pintype "passive"))
    )
    (net (code "4") (name "/BOOT0") (class "Default")
      (node (ref "R1") (pin "2") (pinfunction "2_2") (pintype "passive"))
      (node (ref "SW1") (pin "1") (pinfunction "A1_1") (pintype "passive"))
      (node (ref "U1") (pin "138") (pinfunction "BOOT0_138") (pintype "passive"))
    )
    (net (code "5") (name "/BOOT1") (class "Default")
      (node (ref "R2") (pin "2") (pinfunction "2_2") (pintype "passive"))
      (node (ref "SW1") (pin "2") (pinfunction "A2_2") (pintype "passive"))
      (node (ref "U1") (pin "48") (pinfunction "PB2_48") (pintype "passive"))
    )
    (net (code "6") (name "/CAP-SENS1") (class "Default")
      (node (ref "CN3") (pin "1") (pinfunction "1_1") (pintype "passive"))
      (node (ref "CN3") (pin "2") (pinfunction "2_2") (pintype "passive"))
      (node (ref "U32") (pin "26") (pinfunction "IO4_26") (pintype "passive"))
    )
    (net (code "7") (name "/CAP-SENS2") (class "Default")
      (node (ref "CN3") (pin "3") (pinfunction "3_3") (pintype "passive"))
      (node (ref "CN3") (pin "4") (pinfunction "4_4") (pintype "passive"))
      (node (ref "U32") (pin "24") (pinfunction "IO2_24") (pintype "passive"))
    )
    (net (code "8") (name "/CP-RST") (class "Default")
      (node (ref "U38") (pin "2") (pinfunction "2_2") (pintype "passive"))
    )
    (net (code "9") (name "/DM1") (class "Default")
      (node (ref "CN1") (pin "3") (pinfunction "3_3") (pintype "passive"))
      (node (ref "CN17") (pin "1") (pinfunction "1_1") (pintype "passive"))
      (node (ref "U25") (pin "10") (pinfunction "DM1_10") (pintype "passive"))
    )
    (net (code "10") (name "/DM2") (class "Default")
      (node (ref "CN15") (pin "1") (pinfunction "1_1") (pintype "passive"))
      (node (ref "CN2") (pin "3") (pinfunction "3_3") (pintype "passive"))
      (node (ref "U25") (pin "8") (pinfunction "DM2_8") (pintype "passive"))
    )
    (net (code "11") (name "/DM3") (class "Default")
      (node (ref "CN19") (pin "1") (pinfunction "1_1") (pintype "passive"))
      (node (ref "U25") (pin "6") (pinfunction "DM3_6") (pintype "passive"))
      (node (ref "U37") (pin "5") (pinfunction "D-_5") (pintype "passive"))
    )
    (net (code "12") (name "/DM4") (class "Default")
      (node (ref "CN10") (pin "1") (pinfunction "1_1") (pintype "passive"))
      (node (ref "R13") (pin "1") (pinfunction "1_1") (pintype "passive"))
      (node (ref "U22") (pin "A7") (pinfunction "DN1_A7") (pintype "passive"))
      (node (ref "U22") (pin "B7") (pinfunction "DN2_B7") (pintype "passive"))
      (node (ref "U25") (pin "4") (pinfunction "DM4_4") (pintype "passive"))
    )
    (net (code "13") (name "/DMU") (class "Default")
      (node (ref "U21") (pin "A6") (pinfunction "DP1_A6") (pintype "passive"))
      (node (ref "U21") (pin "B7") (pinfunction "DN2_B7") (pintype "passive"))
      (node (ref "U25") (pin "15") (pinfunction "DMU_15") (pintype "passive"))
    )
    (net (code "14") (name "/DP") (class "Default")
      (node (ref "CN11") (pin "1") (pinfunction "1_1") (pintype "passive"))
      (node (ref "R12") (pin "1") (pinfunction "1_1") (pintype "passive"))
      (node (ref "U22") (pin "A6") (pinfunction "DP1_A6") (pintype "passive"))
      (node (ref "U22") (pin "B6") (pinfunction "DP2_B6") (pintype "passive"))
      (node (ref "U25") (pin "5") (pinfunction "DP4_5") (pintype "passive"))
    )
    (net (code "15") (name "/DP1") (class "Default")
      (node (ref "CN1") (pin "2") (pinfunction "2_2") (pintype "passive"))
      (node (ref "CN16") (pin "1") (pinfunction "1_1") (pintype "passive"))
      (node (ref "U25") (pin "11") (pinfunction "DP1_11") (pintype "passive"))
    )
    (net (code "16") (name "/DP2") (class "Default")
      (node (ref "CN14") (pin "1") (pinfunction "1_1") (pintype "passive"))
      (node (ref "CN2") (pin "2") (pinfunction "2_2") (pintype "passive"))
      (node (ref "U25") (pin "9") (pinfunction "DP2_9") (pintype "passive"))
    )
    (net (code "17") (name "/DP3") (class "Default")
      (node (ref "CN18") (pin "1") (pinfunction "1_1") (pintype "passive"))
      (node (ref "U25") (pin "7") (pinfunction "DP3_7") (pintype "passive"))
      (node (ref "U37") (pin "4") (pinfunction "D+_4") (pintype "passive"))
    )
    (net (code "18") (name "/DPU") (class "Default")
      (node (ref "U21") (pin "A7") (pinfunction "DN1_A7") (pintype "passive"))
      (node (ref "U21") (pin "B6") (pinfunction "DP2_B6") (pintype "passive"))
      (node (ref "U25") (pin "16") (pinfunction "DPU_16") (pintype "passive"))
    )
    (net (code "19") (name "/ESC") (class "Default")
      (node (ref "U1") (pin "56") (pinfunction "PG0_56") (pintype "passive"))
      (node (ref "U3") (pin "7") (pinfunction "AUX_CL_7") (pintype "passive"))
    )
    (net (code "20") (name "/ESD") (class "Default")
      (node (ref "U1") (pin "57") (pinfunction "PG1_57") (pintype "passive"))
      (node (ref "U3") (pin "21") (pinfunction "AUX_DA_21") (pintype "passive"))
    )
    (net (code "21") (name "/ESP-EN") (class "Default")
      (node (ref "U27") (pin "2") (pinfunction "2_2") (pintype "passive"))
      (node (ref "U32") (pin "3") (pinfunction "EN_3") (pintype "passive"))
    )
    (net (code "22") (name "/ESP-RXD0") (class "Default")
      (node (ref "CN13") (pin "1") (pinfunction "1_1") (pintype "passive"))
      (node (ref "R21") (pin "2") (pinfunction "2_2") (pintype "passive"))
      (node (ref "U32") (pin "34") (pinfunction "RXD0_34") (pintype "passive"))
    )
    (net (code "23") (name "/ESP-SCL") (class "Default")
      (node (ref "U1") (pin "11") (pinfunction "PF1_11") (pintype "passive"))
      (node (ref "U32") (pin "36") (pinfunction "IO22_36") (pintype "passive"))
    )
    (net (code "24") (name "/ESP-SDA") (class "Default")
      (node (ref "U1") (pin "10") (pinfunction "PF0_10") (pintype "passive"))
      (node (ref "U32") (pin "33") (pinfunction "IO21_33") (pintype "passive"))
    )
    (net (code "25") (name "/ESP-TXD0") (class "Default")
      (node (ref "CN12") (pin "1") (pinfunction "1_1") (pintype "passive"))
      (node (ref "R22") (pin "2") (pinfunction "2_2") (pintype "passive"))
      (node (ref "U32") (pin "35") (pinfunction "TXD0_35") (pintype "passive"))
    )
    (net (code "26") (name "/FSYNC") (class "Default")
      (node (ref "R5") (pin "2") (pinfunction "2_2") (pintype "passive"))
      (node (ref "U1") (pin "54") (pinfunction "PF14_54") (pintype "passive"))
      (node (ref "U3") (pin "11") (pinfunction "FSYNC_11") (pintype "passive"))
    )
    (net (code "27") (name "/GYRO-SCL") (class "Default")
      (node (ref "R8") (pin "2") (pinfunction "2_2") (pintype "passive"))
      (node (ref "U1") (pin "136") (pinfunction "PB6_136") (pintype "passive"))
      (node (ref "U3") (pin "23") (pinfunction "SCL/SCLK_23") (pintype "passive"))
    )
    (net (code "28") (name "/GYRO-SDA") (class "Default")
      (node (ref "R9") (pin "2") (pinfunction "2_2") (pintype "passive"))
      (node (ref "U1") (pin "137") (pinfunction "PB7_137") (pintype "passive"))
      (node (ref "U3") (pin "24") (pinfunction "SDA/SDI_24") (pintype "passive"))
    )
    (net (code "29") (name "/INT") (class "Default")
      (node (ref "U1") (pin "53") (pinfunction "PF13_53") (pintype "passive"))
      (node (ref "U3") (pin "12") (pinfunction "INT_12") (pintype "passive"))
    )
    (net (code "30") (name "/IO0") (class "Default")
      (node (ref "U26") (pin "2") (pinfunction "2_2") (pintype "passive"))
      (node (ref "U32") (pin "25") (pinfunction "IO0_25") (pintype "passive"))
    )
    (net (code "31") (name "/MCU-CAP-SENS1") (class "Default")
      (node (ref "R18") (pin "1") (pinfunction "1_1") (pintype "passive"))
      (node (ref "U1") (pin "37") (pinfunction "PA3_37") (pintype "passive"))
      (node (ref "U32") (pin "6") (pinfunction "IO34_6") (pintype "passive"))
    )
    (net (code "32") (name "/MCU-CAP-SENS2") (class "Default")
      (node (ref "R19") (pin "1") (pinfunction "1_1") (pintype "passive"))
      (node (ref "U1") (pin "40") (pinfunction "PA4_40") (pintype "passive"))
      (node (ref "U32") (pin "7") (pinfunction "IO35_7") (pintype "passive"))
    )
    (net (code "33") (name "/PA11") (class "Default")
      (node (ref "R13") (pin "2") (pinfunction "2_2") (pintype "passive"))
      (node (ref "U1") (pin "103") (pinfunction "PA11_103") (pintype "passive"))
    )
    (net (code "34") (name "/PA12") (class "Default")
      (node (ref "R12") (pin "2") (pinfunction "2_2") (pintype "passive"))
      (node (ref "R14") (pin "2") (pinfunction "2_2") (pintype "passive"))
      (node (ref "U1") (pin "104") (pinfunction "PA12_104") (pintype "passive"))
    )
    (net (code "35") (name "/PG15") (class "Default")
      (node (ref "R15") (pin "2") (pinfunction "2_2") (pintype "passive"))
      (node (ref "U1") (pin "132") (pinfunction "PG15_132") (pintype "passive"))
    )
    (net (code "36") (name "/REGOUT") (class "Default")
      (node (ref "U19") (pin "1") (pinfunction "1_1") (pintype "passive"))
      (node (ref "U3") (pin "10") (pinfunction "REGOUT_10") (pintype "passive"))
    )
    (net (code "37") (name "/RESET") (class "Default")
      (node (ref "U1") (pin "25") (pinfunction "NRST_25") (pintype "passive"))
      (node (ref "U24") (pin "2") (pinfunction "2_2") (pintype "passive"))
    )
    (net (code "38") (name "/SBC-RXD") (class "Default")
      (node (ref "R24") (pin "2") (pinfunction "2_2") (pintype "passive"))
      (node (ref "U1") (pin "112") (pinfunction "PC11_112") (pintype "passive"))
    )
    (net (code "39") (name "/SBC-TXD") (class "Default")
      (node (ref "R23") (pin "2") (pinfunction "2_2") (pintype "passive"))
      (node (ref "U1") (pin "111") (pinfunction "PC10_111") (pintype "passive"))
    )
    (net (code "40") (name "/STM-RXD0") (class "Default")
      (node (ref "R22") (pin "1") (pinfunction "1_1") (pintype "passive"))
      (node (ref "U1") (pin "116") (pinfunction "PD2_116") (pintype "passive"))
    )
    (net (code "41") (name "/STM-TXD0") (class "Default")
      (node (ref "R21") (pin "1") (pinfunction "1_1") (pintype "passive"))
      (node (ref "U1") (pin "113") (pinfunction "PC12_113") (pintype "passive"))
    )
    (net (code "42") (name "/SWCLK") (class "Default")
      (node (ref "J1") (pin "2") (pinfunction "2_2") (pintype "passive"))
      (node (ref "U1") (pin "109") (pinfunction "PA14_109") (pintype "passive"))
    )
    (net (code "43") (name "/SWDIO") (class "Default")
      (node (ref "J1") (pin "3") (pinfunction "3_3") (pintype "passive"))
      (node (ref "U1") (pin "105") (pinfunction "PA13_105") (pintype "passive"))
    )
    (net (code "44") (name "/TP-1") (class "Default")
      (node (ref "CN4") (pin "1") (pinfunction "1_1") (pintype "passive"))
      (node (ref "U1") (pin "49") (pinfunction "PF11_49") (pintype "passive"))
    )
    (net (code "45") (name "/TP-2") (class "Default")
      (node (ref "CN5") (pin "1") (pinfunction "1_1") (pintype "passive"))
      (node (ref "U1") (pin "50") (pinfunction "PF12_50") (pintype "passive"))
    )
    (net (code "46") (name "/TP-3") (class "Default")
      (node (ref "CN7") (pin "1") (pinfunction "1_1") (pintype "passive"))
      (node (ref "U1") (pin "59") (pinfunction "PE8_59") (pintype "passive"))
    )
    (net (code "47") (name "/TP-4") (class "Default")
      (node (ref "CN6") (pin "1") (pinfunction "1_1") (pintype "passive"))
      (node (ref "U1") (pin "60") (pinfunction "PE9_60") (pintype "passive"))
    )
    (net (code "48") (name "/TP-5") (class "Default")
      (node (ref "CN9") (pin "1") (pinfunction "1_1") (pintype "passive"))
      (node (ref "U1") (pin "63") (pinfunction "PE10_63") (pintype "passive"))
    )
    (net (code "49") (name "/TP-6") (class "Default")
      (node (ref "CN8") (pin "1") (pinfunction "1_1") (pintype "passive"))
      (node (ref "U1") (pin "64") (pinfunction "PE11_64") (pintype "passive"))
    )
    (net (code "50") (name "/nCS") (class "Default")
      (node (ref "R7") (pin "2") (pinfunction "2_2") (pintype "passive"))
      (node (ref "U1") (pin "58") (pinfunction "PE7_58") (pintype "passive"))
      (node (ref "U3") (pin "22") (pinfunction "nCS_22") (pintype "passive"))
    )
    (net (code "51") (name "GND") (class "Default")
      (node (ref "CN1") (pin "1") (pinfunction "1_1") (pintype "passive"))
      (node (ref "CN2") (pin "1") (pinfunction "1_1") (pintype "passive"))
      (node (ref "J1") (pin "1") (pinfunction "1_1") (pintype "passive"))
      (node (ref "R1") (pin "1") (pinfunction "1_1") (pintype "passive"))
      (node (ref "R10") (pin "2") (pinfunction "2_2") (pintype "passive"))
      (node (ref "R11") (pin "1") (pinfunction "1_1") (pintype "passive"))
      (node (ref "R16") (pin "2") (pinfunction "2_2") (pintype "passive"))
      (node (ref "R17") (pin "2") (pinfunction "2_2") (pintype "passive"))
      (node (ref "R2") (pin "1") (pinfunction "1_1") (pintype "passive"))
      (node (ref "R20") (pin "2") (pinfunction "2_2") (pintype "passive"))
      (node (ref "R27") (pin "1") (pinfunction "1_1") (pintype "passive"))
      (node (ref "R30") (pin "2") (pinfunction "2_2") (pintype "passive"))
      (node (ref "R31") (pin "1") (pinfunction "1_1") (pintype "passive"))
      (node (ref "R38") (pin "2") (pinfunction "2_2") (pintype "passive"))
      (node (ref "R39") (pin "1") (pinfunction "1_1") (pintype "passive"))
      (node (ref "R5") (pin "1") (pinfunction "1_1") (pintype "passive"))
      (node (ref "R6") (pin "1") (pinfunction "1_1") (pintype "passive"))
      (node (ref "U1") (pin "107") (pinfunction "VSS_107") (pintype "passive"))
      (node (ref "U1") (pin "120") (pinfunction "VSS_120") (pintype "passive"))
      (node (ref "U1") (pin "130") (pinfunction "VSS_130") (pintype "passive"))
      (node (ref "U1") (pin "16") (pinfunction "VSS_16") (pintype "passive"))
      (node (ref "U1") (pin "38") (pinfunction "VSS_38") (pintype "passive"))
      (node (ref "U1") (pin "51") (pinfunction "VSS_51") (pintype "passive"))
      (node (ref "U1") (pin "61") (pinfunction "VSS_61") (pintype "passive"))
      (node (ref "U1") (pin "83") (pinfunction "VSS_83") (pintype "passive"))
      (node (ref "U1") (pin "94") (pinfunction "VSS_94") (pintype "passive"))
      (node (ref "U10") (pin "1") (pinfunction "1_1") (pintype "passive"))
      (node (ref "U11") (pin "1") (pinfunction "1_1") (pintype "passive"))
      (node (ref "U12") (pin "1") (pinfunction "1_1") (pintype "passive"))
      (node (ref "U13") (pin "1") (pinfunction "1_1") (pintype "passive"))
      (node (ref "U14") (pin "1") (pinfunction "1_1") (pintype "passive"))
      (node (ref "U15") (pin "1") (pinfunction "1_1") (pintype "passive"))
      (node (ref "U16") (pin "1") (pinfunction "1_1") (pintype "passive"))
      (node (ref "U17") (pin "1") (pinfunction "1_1") (pintype "passive"))
      (node (ref "U18") (pin "2") (pinfunction "2_2") (pintype "passive"))
      (node (ref "U19") (pin "2") (pinfunction "2_2") (pintype "passive"))
      (node (ref "U2") (pin "1") (pinfunction "1_1") (pintype "passive"))
      (node (ref "U20") (pin "2") (pinfunction "2_2") (pintype "passive"))
      (node (ref "U21") (pin "0") (pinfunction "SH_0") (pintype "passive"))
      (node (ref "U21") (pin "1") (pinfunction "SH_1") (pintype "passive"))
      (node (ref "U21") (pin "2") (pinfunction "SH_2") (pintype "passive"))
      (node (ref "U21") (pin "3") (pinfunction "SH_3") (pintype "passive"))
      (node (ref "U21") (pin "A1") (pinfunction "GND_A1") (pintype "passive"))
      (node (ref "U21") (pin "A12") (pinfunction "GND_A12") (pintype "passive"))
      (node (ref "U21") (pin "B1") (pinfunction "GND_B1") (pintype "passive"))
      (node (ref "U21") (pin "B12") (pinfunction "GND_B12") (pintype "passive"))
      (node (ref "U22") (pin "0") (pinfunction "SH_0") (pintype "passive"))
      (node (ref "U22") (pin "1") (pinfunction "SH_1") (pintype "passive"))
      (node (ref "U22") (pin "2") (pinfunction "SH_2") (pintype "passive"))
      (node (ref "U22") (pin "3") (pinfunction "SH_3") (pintype "passive"))
      (node (ref "U22") (pin "A1") (pinfunction "GND_A1") (pintype "passive"))
      (node (ref "U22") (pin "A12") (pinfunction "GND_A12") (pintype "passive"))
      (node (ref "U22") (pin "B1") (pinfunction "GND_B1") (pintype "passive"))
      (node (ref "U22") (pin "B12") (pinfunction "GND_B12") (pintype "passive"))
      (node (ref "U23") (pin "1") (pinfunction "ADJ/GND_1") (pintype "passive"))
      (node (ref "U24") (pin "3") (pinfunction "3_3") (pintype "passive"))
      (node (ref "U25") (pin "1") (pinfunction "VSS_1") (pintype "passive"))
      (node (ref "U26") (pin "3") (pinfunction "3_3") (pintype "passive"))
      (node (ref "U27") (pin "3") (pinfunction "3_3") (pintype "passive"))
      (node (ref "U28") (pin "2") (pinfunction "2_2") (pintype "passive"))
      (node (ref "U29") (pin "2") (pinfunction "2_2") (pintype "passive"))
      (node (ref "U3") (pin "18") (pinfunction "GND_18") (pintype "passive"))
      (node (ref "U3") (pin "20") (pinfunction "RESV_20") (pintype "passive"))
      (node (ref "U30") (pin "2") (pinfunction "2_2") (pintype "passive"))
      (node (ref "U31") (pin "2") (pinfunction "2_2") (pintype "passive"))
      (node (ref "U32") (pin "1") (pinfunction "GND_1") (pintype "passive"))
      (node (ref "U32") (pin "15") (pinfunction "GND_15") (pintype "passive"))
      (node (ref "U32") (pin "38") (pinfunction "GND_38") (pintype "passive"))
      (node (ref "U32") (pin "39") (pinfunction "GND_39") (pintype "passive"))
      (node (ref "U33") (pin "2") (pinfunction "2_2") (pintype "passive"))
      (node (ref "U34") (pin "2") (pinfunction "2_2") (pintype "passive"))
      (node (ref "U35") (pin "2") (pinfunction "2_2") (pintype "passive"))
      (node (ref "U36") (pin "1") (pinfunction "1_1") (pintype "passive"))
      (node (ref "U37") (pin "29") (pinfunction "EP_29") (pintype "passive"))
      (node (ref "U37") (pin "3") (pinfunction "GND_3") (pintype "passive"))
      (node (ref "U39") (pin "1") (pinfunction "1_1") (pintype "passive"))
      (node (ref "U4") (pin "1") (pinfunction "1_1") (pintype "passive"))
      (node (ref "U40") (pin "1") (pinfunction "1_1") (pintype "passive"))
      (node (ref "U5") (pin "1") (pinfunction "1_1") (pintype "passive"))
      (node (ref "U6") (pin "1") (pinfunction "1_1") (pintype "passive"))
      (node (ref "U7") (pin "1") (pinfunction "1_1") (pintype "passive"))
      (node (ref "U8") (pin "1") (pinfunction "1_1") (pintype "passive"))
      (node (ref "U9") (pin "1") (pinfunction "1_1") (pintype "passive"))
    )
    (net (code "52") (name "Net-(LED1-Pad2)") (class "Default")
      (node (ref "LED1") (pin "2") (pinfunction "2_2") (pintype "passive"))
      (node (ref "R15") (pin "1") (pinfunction "1_1") (pintype "passive"))
    )
    (net (code "53") (name "Net-(LED2-Pad2)") (class "Default")
      (node (ref "LED2") (pin "2") (pinfunction "2_2") (pintype "passive"))
      (node (ref "R16") (pin "1") (pinfunction "1_1") (pintype "passive"))
    )
    (net (code "54") (name "Net-(LED3-Pad1)") (class "Default")
      (node (ref "LED3") (pin "1") (pinfunction "1_1") (pintype "passive"))
      (node (ref "R18") (pin "2") (pinfunction "2_2") (pintype "passive"))
    )
    (net (code "55") (name "Net-(LED3-Pad2)") (class "Default")
      (node (ref "LED3") (pin "2") (pinfunction "2_2") (pintype "passive"))
      (node (ref "R17") (pin "1") (pinfunction "1_1") (pintype "passive"))
    )
    (net (code "56") (name "Net-(LED4-Pad1)") (class "Default")
      (node (ref "LED4") (pin "1") (pinfunction "1_1") (pintype "passive"))
      (node (ref "R19") (pin "2") (pinfunction "2_2") (pintype "passive"))
    )
    (net (code "57") (name "Net-(LED4-Pad2)") (class "Default")
      (node (ref "LED4") (pin "2") (pinfunction "2_2") (pintype "passive"))
      (node (ref "R20") (pin "1") (pinfunction "1_1") (pintype "passive"))
    )
    (net (code "58") (name "Net-(LED5-Pad1)") (class "Default")
      (node (ref "LED5") (pin "1") (pinfunction "1_1") (pintype "passive"))
      (node (ref "LED6") (pin "2") (pinfunction "2_2") (pintype "passive"))
      (node (ref "R29") (pin "2") (pinfunction "2_2") (pintype "passive"))
    )
    (net (code "59") (name "Net-(LED7-Pad2)") (class "Default")
      (node (ref "LED7") (pin "2") (pinfunction "2_2") (pintype "passive"))
      (node (ref "LED8") (pin "1") (pinfunction "1_1") (pintype "passive"))
      (node (ref "R28") (pin "2") (pinfunction "2_2") (pintype "passive"))
    )
    (net (code "60") (name "Net-(LED9-Pad2)") (class "Default")
      (node (ref "LED9") (pin "2") (pinfunction "2_2") (pintype "passive"))
      (node (ref "R30") (pin "1") (pinfunction "1_1") (pintype "passive"))
    )
    (net (code "61") (name "Net-(LED10-Pad1)") (class "Default")
      (node (ref "LED10") (pin "1") (pinfunction "1_1") (pintype "passive"))
      (node (ref "R40") (pin "2") (pinfunction "2_2") (pintype "passive"))
    )
    (net (code "62") (name "Net-(LED11-Pad1)") (class "Default")
      (node (ref "LED11") (pin "1") (pinfunction "1_1") (pintype "passive"))
      (node (ref "R36") (pin "2") (pinfunction "2_2") (pintype "passive"))
    )
    (net (code "63") (name "Net-(R23-Pad1)") (class "Default")
      (node (ref "R23") (pin "1") (pinfunction "1_1") (pintype "passive"))
      (node (ref "R35") (pin "1") (pinfunction "1_1") (pintype "passive"))
    )
    (net (code "64") (name "Net-(R24-Pad1)") (class "Default")
      (node (ref "R24") (pin "1") (pinfunction "1_1") (pintype "passive"))
      (node (ref "R26") (pin "1") (pinfunction "1_1") (pintype "passive"))
    )
    (net (code "65") (name "Net-(SW1-B1)") (class "Default")
      (node (ref "R3") (pin "2") (pinfunction "2_2") (pintype "passive"))
      (node (ref "SW1") (pin "4") (pinfunction "B1_4") (pintype "passive"))
    )
    (net (code "66") (name "Net-(SW1-B2)") (class "Default")
      (node (ref "R4") (pin "2") (pinfunction "2_2") (pintype "passive"))
      (node (ref "SW1") (pin "3") (pinfunction "B2_3") (pintype "passive"))
    )
    (net (code "67") (name "Net-(U1-PH0)") (class "Default")
      (node (ref "CRYSTAL1") (pin "1") (pinfunction "1_1") (pintype "passive"))
      (node (ref "U1") (pin "23") (pinfunction "PH0_23") (pintype "passive"))
      (node (ref "U2") (pin "2") (pinfunction "2_2") (pintype "passive"))
    )
    (net (code "68") (name "Net-(U1-PH1)") (class "Default")
      (node (ref "CRYSTAL1") (pin "2") (pinfunction "2_2") (pintype "passive"))
      (node (ref "U1") (pin "24") (pinfunction "PH1_24") (pintype "passive"))
      (node (ref "U4") (pin "2") (pinfunction "2_2") (pintype "passive"))
    )
    (net (code "69") (name "Net-(U1-VBAT)") (class "Default")
      (node (ref "U1") (pin "6") (pinfunction "VBAT_6") (pintype "passive"))
      (node (ref "U6") (pin "2") (pinfunction "2_2") (pintype "passive"))
    )
    (net (code "70") (name "Net-(U1-VCAP_1)") (class "Default")
      (node (ref "U1") (pin "71") (pinfunction "VCAP_1_71") (pintype "passive"))
      (node (ref "U10") (pin "2") (pinfunction "2_2") (pintype "passive"))
    )
    (net (code "71") (name "Net-(U1-VCAP_2)") (class "Default")
      (node (ref "U1") (pin "106") (pinfunction "VCAP_2_106") (pintype "passive"))
      (node (ref "U17") (pin "2") (pinfunction "2_2") (pintype "passive"))
    )
    (net (code "72") (name "Net-(U21-CC1)") (class "Default")
      (node (ref "R39") (pin "2") (pinfunction "2_2") (pintype "passive"))
      (node (ref "U21") (pin "A5") (pinfunction "CC1_A5") (pintype "passive"))
    )
    (net (code "73") (name "Net-(U21-CC2)") (class "Default")
      (node (ref "R38") (pin "1") (pinfunction "1_1") (pintype "passive"))
      (node (ref "U21") (pin "B5") (pinfunction "CC2_B5") (pintype "passive"))
    )
    (net (code "74") (name "Net-(U22-CC1)") (class "Default")
      (node (ref "R11") (pin "2") (pinfunction "2_2") (pintype "passive"))
      (node (ref "U22") (pin "A5") (pinfunction "CC1_A5") (pintype "passive"))
    )
    (net (code "75") (name "Net-(U22-CC2)") (class "Default")
      (node (ref "R10") (pin "1") (pinfunction "1_1") (pintype "passive"))
      (node (ref "U22") (pin "B5") (pinfunction "CC2_B5") (pintype "passive"))
    )
    (net (code "76") (name "Net-(U25-BUSJ)") (class "Default")
      (node (ref "R33") (pin "1") (pinfunction "1_1") (pintype "passive"))
      (node (ref "U25") (pin "19") (pinfunction "BUSJ_19") (pintype "passive"))
    )
    (net (code "77") (name "Net-(U25-DRV)") (class "Default")
      (node (ref "LED5") (pin "2") (pinfunction "2_2") (pintype "passive"))
      (node (ref "LED6") (pin "1") (pinfunction "1_1") (pintype "passive"))
      (node (ref "LED7") (pin "1") (pinfunction "1_1") (pintype "passive"))
      (node (ref "LED8") (pin "2") (pinfunction "2_2") (pintype "passive"))
      (node (ref "LED9") (pin "1") (pinfunction "1_1") (pintype "passive"))
      (node (ref "U25") (pin "22") (pinfunction "DRV_22") (pintype "passive"))
    )
    (net (code "78") (name "Net-(U25-LED1)") (class "Default")
      (node (ref "R28") (pin "1") (pinfunction "1_1") (pintype "passive"))
      (node (ref "U25") (pin "23") (pinfunction "LED1_23") (pintype "passive"))
    )
    (net (code "79") (name "Net-(U25-LED2)") (class "Default")
      (node (ref "R29") (pin "1") (pinfunction "1_1") (pintype "passive"))
      (node (ref "U25") (pin "24") (pinfunction "LED2_24") (pintype "passive"))
    )
    (net (code "80") (name "Net-(U25-REXT)") (class "Default")
      (node (ref "R27") (pin "2") (pinfunction "2_2") (pintype "passive"))
      (node (ref "U25") (pin "14") (pinfunction "REXT_14") (pintype "passive"))
    )
    (net (code "81") (name "Net-(U25-VBUSM)") (class "Default")
      (node (ref "R31") (pin "2") (pinfunction "2_2") (pintype "passive"))
      (node (ref "R32") (pin "1") (pinfunction "1_1") (pintype "passive"))
      (node (ref "U25") (pin "18") (pinfunction "VBUSM_18") (pintype "passive"))
    )
    (net (code "82") (name "Net-(U25-XIN)") (class "Default")
      (node (ref "CRYSTAL2") (pin "1") (pinfunction "1_1") (pintype "passive"))
      (node (ref "U25") (pin "3") (pinfunction "XIN_3") (pintype "passive"))
    )
    (net (code "83") (name "Net-(U25-XOUT)") (class "Default")
      (node (ref "CRYSTAL2") (pin "2") (pinfunction "2_2") (pintype "passive"))
      (node (ref "U25") (pin "2") (pinfunction "XOUT_2") (pintype "passive"))
    )
    (net (code "84") (name "Net-(U25-XRSTJ)") (class "Default")
      (node (ref "R34") (pin "1") (pinfunction "1_1") (pintype "passive"))
      (node (ref "U25") (pin "17") (pinfunction "XRSTJ_17") (pintype "passive"))
    )
    (net (code "85") (name "Net-(U37-DTR)") (class "Default")
      (node (ref "U37") (pin "28") (pinfunction "DTR_28") (pintype "passive"))
      (node (ref "U38") (pin "1") (pinfunction "1_1") (pintype "passive"))
    )
    (net (code "86") (name "Net-(U37-RSTb)") (class "Default")
      (node (ref "R37") (pin "1") (pinfunction "1_1") (pintype "passive"))
      (node (ref "U37") (pin "9") (pinfunction "RSTb_9") (pintype "passive"))
    )
    (net (code "87") (name "Net-(U37-RXD)") (class "Default")
      (node (ref "LED10") (pin "2") (pinfunction "2_2") (pintype "passive"))
      (node (ref "R35") (pin "2") (pinfunction "2_2") (pintype "passive"))
      (node (ref "U37") (pin "25") (pinfunction "RXD_25") (pintype "passive"))
    )
    (net (code "88") (name "Net-(U37-TXD)") (class "Default")
      (node (ref "LED11") (pin "2") (pinfunction "2_2") (pintype "passive"))
      (node (ref "R26") (pin "2") (pinfunction "2_2") (pintype "passive"))
      (node (ref "U37") (pin "26") (pinfunction "TXD_26") (pintype "passive"))
    )
    (net (code "89") (name "Net-(U37-VDD)") (class "Default")
      (node (ref "U36") (pin "2") (pinfunction "2_2") (pintype "passive"))
      (node (ref "U37") (pin "6") (pinfunction "VDD_6") (pintype "passive"))
    )
    (net (code "90") (name "VCC") (class "Default")
      (node (ref "J1") (pin "4") (pinfunction "4_4") (pintype "passive"))
      (node (ref "LED1") (pin "1") (pinfunction "1_1") (pintype "passive"))
      (node (ref "LED2") (pin "1") (pinfunction "1_1") (pintype "passive"))
      (node (ref "R14") (pin "1") (pinfunction "1_1") (pintype "passive"))
      (node (ref "R3") (pin "1") (pinfunction "1_1") (pintype "passive"))
      (node (ref "R33") (pin "2") (pinfunction "2_2") (pintype "passive"))
      (node (ref "R34") (pin "2") (pinfunction "2_2") (pintype "passive"))
      (node (ref "R36") (pin "1") (pinfunction "1_1") (pintype "passive"))
      (node (ref "R37") (pin "2") (pinfunction "2_2") (pintype "passive"))
      (node (ref "R4") (pin "1") (pinfunction "1_1") (pintype "passive"))
      (node (ref "R40") (pin "1") (pinfunction "1_1") (pintype "passive"))
      (node (ref "R7") (pin "1") (pinfunction "1_1") (pintype "passive"))
      (node (ref "R8") (pin "1") (pinfunction "1_1") (pintype "passive"))
      (node (ref "R9") (pin "1") (pinfunction "1_1") (pintype "passive"))
      (node (ref "U1") (pin "108") (pinfunction "VDD_108") (pintype "passive"))
      (node (ref "U1") (pin "121") (pinfunction "VDD_121") (pintype "passive"))
      (node (ref "U1") (pin "131") (pinfunction "VDD_131") (pintype "passive"))
      (node (ref "U1") (pin "143") (pinfunction "PDR_ON_143") (pintype "passive"))
      (node (ref "U1") (pin "144") (pinfunction "VDD_144") (pintype "passive"))
      (node (ref "U1") (pin "17") (pinfunction "VDD_17") (pintype "passive"))
      (node (ref "U1") (pin "30") (pinfunction "VDD_30") (pintype "passive"))
      (node (ref "U1") (pin "33") (pinfunction "VDDA_33") (pintype "passive"))
      (node (ref "U1") (pin "39") (pinfunction "VDD_39") (pintype "passive"))
      (node (ref "U1") (pin "52") (pinfunction "VDD_52") (pintype "passive"))
      (node (ref "U1") (pin "62") (pinfunction "VDD_62") (pintype "passive"))
      (node (ref "U1") (pin "72") (pinfunction "VDD_72") (pintype "passive"))
      (node (ref "U1") (pin "84") (pinfunction "VDD_84") (pintype "passive"))
      (node (ref "U1") (pin "95") (pinfunction "VDD_95") (pintype "passive"))
      (node (ref "U11") (pin "2") (pinfunction "2_2") (pintype "passive"))
      (node (ref "U12") (pin "2") (pinfunction "2_2") (pintype "passive"))
      (node (ref "U13") (pin "2") (pinfunction "2_2") (pintype "passive"))
      (node (ref "U14") (pin "2") (pinfunction "2_2") (pintype "passive"))
      (node (ref "U15") (pin "2") (pinfunction "2_2") (pintype "passive"))
      (node (ref "U16") (pin "2") (pinfunction "2_2") (pintype "passive"))
      (node (ref "U18") (pin "1") (pinfunction "1_1") (pintype "passive"))
      (node (ref "U20") (pin "1") (pinfunction "1_1") (pintype "passive"))
      (node (ref "U23") (pin "2") (pinfunction "VOUT_2") (pintype "passive"))
      (node (ref "U23") (pin "4") (pinfunction "VOUT_4") (pintype "passive"))
      (node (ref "U25") (pin "13") (pinfunction "VD33_13") (pintype "passive"))
      (node (ref "U25") (pin "21") (pinfunction "VD33_O_21") (pintype "passive"))
      (node (ref "U25") (pin "26") (pinfunction "OVCJ_26") (pintype "passive"))
      (node (ref "U28") (pin "1") (pinfunction "1_1") (pintype "passive"))
      (node (ref "U3") (pin "1") (pinfunction "NC_1") (pintype "passive"))
      (node (ref "U3") (pin "13") (pinfunction "VDD_13") (pintype "passive"))
      (node (ref "U3") (pin "8") (pinfunction "VDDIO_8") (pintype "passive"))
      (node (ref "U30") (pin "1") (pinfunction "1_1") (pintype "passive"))
      (node (ref "U32") (pin "2") (pinfunction "3V3_2") (pintype "passive"))
      (node (ref "U35") (pin "1") (pinfunction "1_1") (pintype "passive"))
      (node (ref "U39") (pin "2") (pinfunction "2_2") (pintype "passive"))
      (node (ref "U40") (pin "2") (pinfunction "2_2") (pintype "passive"))
      (node (ref "U5") (pin "2") (pinfunction "2_2") (pintype "passive"))
      (node (ref "U7") (pin "2") (pinfunction "2_2") (pintype "passive"))
      (node (ref "U8") (pin "2") (pinfunction "2_2") (pintype "passive"))
      (node (ref "U9") (pin "2") (pinfunction "2_2") (pintype "passive"))
    )
    (net (code "91") (name "unconnected-(U1-PA0-Pad34)") (class "Default")
      (node (ref "U1") (pin "34") (pinfunction "PA0_34") (pintype "passive"))
    )
    (net (code "92") (name "unconnected-(U1-PA1-Pad35)") (class "Default")
      (node (ref "U1") (pin "35") (pinfunction "PA1_35") (pintype "passive"))
    )
    (net (code "93") (name "unconnected-(U1-PA2-Pad36)") (class "Default")
      (node (ref "U1") (pin "36") (pinfunction "PA2_36") (pintype "passive"))
    )
    (net (code "94") (name "unconnected-(U1-PA5-Pad41)") (class "Default")
      (node (ref "U1") (pin "41") (pinfunction "PA5_41") (pintype "passive"))
    )
    (net (code "95") (name "unconnected-(U1-PA6-Pad42)") (class "Default")
      (node (ref "U1") (pin "42") (pinfunction "PA6_42") (pintype "passive"))
    )
    (net (code "96") (name "unconnected-(U1-PA7-Pad43)") (class "Default")
      (node (ref "U1") (pin "43") (pinfunction "PA7_43") (pintype "passive"))
    )
    (net (code "97") (name "unconnected-(U1-PA8-Pad100)") (class "Default")
      (node (ref "U1") (pin "100") (pinfunction "PA8_100") (pintype "passive"))
    )
    (net (code "98") (name "unconnected-(U1-PA9-Pad101)") (class "Default")
      (node (ref "U1") (pin "101") (pinfunction "PA9_101") (pintype "passive"))
    )
    (net (code "99") (name "unconnected-(U1-PA10-Pad102)") (class "Default")
      (node (ref "U1") (pin "102") (pinfunction "PA10_102") (pintype "passive"))
    )
    (net (code "100") (name "unconnected-(U1-PA15-Pad110)") (class "Default")
      (node (ref "U1") (pin "110") (pinfunction "PA15_110") (pintype "passive"))
    )
    (net (code "101") (name "unconnected-(U1-PB0-Pad46)") (class "Default")
      (node (ref "U1") (pin "46") (pinfunction "PB0_46") (pintype "passive"))
    )
    (net (code "102") (name "unconnected-(U1-PB1-Pad47)") (class "Default")
      (node (ref "U1") (pin "47") (pinfunction "PB1_47") (pintype "passive"))
    )
    (net (code "103") (name "unconnected-(U1-PB3-Pad133)") (class "Default")
      (node (ref "U1") (pin "133") (pinfunction "PB3_133") (pintype "passive"))
    )
    (net (code "104") (name "unconnected-(U1-PB4-Pad134)") (class "Default")
      (node (ref "U1") (pin "134") (pinfunction "PB4_134") (pintype "passive"))
    )
    (net (code "105") (name "unconnected-(U1-PB5-Pad135)") (class "Default")
      (node (ref "U1") (pin "135") (pinfunction "PB5_135") (pintype "passive"))
    )
    (net (code "106") (name "unconnected-(U1-PB8-Pad139)") (class "Default")
      (node (ref "U1") (pin "139") (pinfunction "PB8_139") (pintype "passive"))
    )
    (net (code "107") (name "unconnected-(U1-PB9-Pad140)") (class "Default")
      (node (ref "U1") (pin "140") (pinfunction "PB9_140") (pintype "passive"))
    )
    (net (code "108") (name "unconnected-(U1-PB10-Pad69)") (class "Default")
      (node (ref "U1") (pin "69") (pinfunction "PB10_69") (pintype "passive"))
    )
    (net (code "109") (name "unconnected-(U1-PB11-Pad70)") (class "Default")
      (node (ref "U1") (pin "70") (pinfunction "PB11_70") (pintype "passive"))
    )
    (net (code "110") (name "unconnected-(U1-PB12-Pad73)") (class "Default")
      (node (ref "U1") (pin "73") (pinfunction "PB12_73") (pintype "passive"))
    )
    (net (code "111") (name "unconnected-(U1-PB13-Pad74)") (class "Default")
      (node (ref "U1") (pin "74") (pinfunction "PB13_74") (pintype "passive"))
    )
    (net (code "112") (name "unconnected-(U1-PB14-Pad75)") (class "Default")
      (node (ref "U1") (pin "75") (pinfunction "PB14_75") (pintype "passive"))
    )
    (net (code "113") (name "unconnected-(U1-PB15-Pad76)") (class "Default")
      (node (ref "U1") (pin "76") (pinfunction "PB15_76") (pintype "passive"))
    )
    (net (code "114") (name "unconnected-(U1-PC0-Pad26)") (class "Default")
      (node (ref "U1") (pin "26") (pinfunction "PC0_26") (pintype "passive"))
    )
    (net (code "115") (name "unconnected-(U1-PC1-Pad27)") (class "Default")
      (node (ref "U1") (pin "27") (pinfunction "PC1_27") (pintype "passive"))
    )
    (net (code "116") (name "unconnected-(U1-PC2-Pad28)") (class "Default")
      (node (ref "U1") (pin "28") (pinfunction "PC2_28") (pintype "passive"))
    )
    (net (code "117") (name "unconnected-(U1-PC3-Pad29)") (class "Default")
      (node (ref "U1") (pin "29") (pinfunction "PC3_29") (pintype "passive"))
    )
    (net (code "118") (name "unconnected-(U1-PC4-Pad44)") (class "Default")
      (node (ref "U1") (pin "44") (pinfunction "PC4_44") (pintype "passive"))
    )
    (net (code "119") (name "unconnected-(U1-PC5-Pad45)") (class "Default")
      (node (ref "U1") (pin "45") (pinfunction "PC5_45") (pintype "passive"))
    )
    (net (code "120") (name "unconnected-(U1-PC6-Pad96)") (class "Default")
      (node (ref "U1") (pin "96") (pinfunction "PC6_96") (pintype "passive"))
    )
    (net (code "121") (name "unconnected-(U1-PC7-Pad97)") (class "Default")
      (node (ref "U1") (pin "97") (pinfunction "PC7_97") (pintype "passive"))
    )
    (net (code "122") (name "unconnected-(U1-PC8-Pad98)") (class "Default")
      (node (ref "U1") (pin "98") (pinfunction "PC8_98") (pintype "passive"))
    )
    (net (code "123") (name "unconnected-(U1-PC9-Pad99)") (class "Default")
      (node (ref "U1") (pin "99") (pinfunction "PC9_99") (pintype "passive"))
    )
    (net (code "124") (name "unconnected-(U1-PC13-Pad7)") (class "Default")
      (node (ref "U1") (pin "7") (pinfunction "PC13_7") (pintype "passive"))
    )
    (net (code "125") (name "unconnected-(U1-PC14-Pad8)") (class "Default")
      (node (ref "U1") (pin "8") (pinfunction "PC14_8") (pintype "passive"))
    )
    (net (code "126") (name "unconnected-(U1-PC15-Pad9)") (class "Default")
      (node (ref "U1") (pin "9") (pinfunction "PC15_9") (pintype "passive"))
    )
    (net (code "127") (name "unconnected-(U1-PD0-Pad114)") (class "Default")
      (node (ref "U1") (pin "114") (pinfunction "PD0_114") (pintype "passive"))
    )
    (net (code "128") (name "unconnected-(U1-PD1-Pad115)") (class "Default")
      (node (ref "U1") (pin "115") (pinfunction "PD1_115") (pintype "passive"))
    )
    (net (code "129") (name "unconnected-(U1-PD3-Pad117)") (class "Default")
      (node (ref "U1") (pin "117") (pinfunction "PD3_117") (pintype "passive"))
    )
    (net (code "130") (name "unconnected-(U1-PD4-Pad118)") (class "Default")
      (node (ref "U1") (pin "118") (pinfunction "PD4_118") (pintype "passive"))
    )
    (net (code "131") (name "unconnected-(U1-PD5-Pad119)") (class "Default")
      (node (ref "U1") (pin "119") (pinfunction "PD5_119") (pintype "passive"))
    )
    (net (code "132") (name "unconnected-(U1-PD6-Pad122)") (class "Default")
      (node (ref "U1") (pin "122") (pinfunction "PD6_122") (pintype "passive"))
    )
    (net (code "133") (name "unconnected-(U1-PD7-Pad123)") (class "Default")
      (node (ref "U1") (pin "123") (pinfunction "PD7_123") (pintype "passive"))
    )
    (net (code "134") (name "unconnected-(U1-PD8-Pad77)") (class "Default")
      (node (ref "U1") (pin "77") (pinfunction "PD8_77") (pintype "passive"))
    )
    (net (code "135") (name "unconnected-(U1-PD9-Pad78)") (class "Default")
      (node (ref "U1") (pin "78") (pinfunction "PD9_78") (pintype "passive"))
    )
    (net (code "136") (name "unconnected-(U1-PD10-Pad79)") (class "Default")
      (node (ref "U1") (pin "79") (pinfunction "PD10_79") (pintype "passive"))
    )
    (net (code "137") (name "unconnected-(U1-PD11-Pad80)") (class "Default")
      (node (ref "U1") (pin "80") (pinfunction "PD11_80") (pintype "passive"))
    )
    (net (code "138") (name "unconnected-(U1-PD12-Pad81)") (class "Default")
      (node (ref "U1") (pin "81") (pinfunction "PD12_81") (pintype "passive"))
    )
    (net (code "139") (name "unconnected-(U1-PD13-Pad82)") (class "Default")
      (node (ref "U1") (pin "82") (pinfunction "PD13_82") (pintype "passive"))
    )
    (net (code "140") (name "unconnected-(U1-PD14-Pad85)") (class "Default")
      (node (ref "U1") (pin "85") (pinfunction "PD14_85") (pintype "passive"))
    )
    (net (code "141") (name "unconnected-(U1-PD15-Pad86)") (class "Default")
      (node (ref "U1") (pin "86") (pinfunction "PD15_86") (pintype "passive"))
    )
    (net (code "142") (name "unconnected-(U1-PE0-Pad141)") (class "Default")
      (node (ref "U1") (pin "141") (pinfunction "PE0_141") (pintype "passive"))
    )
    (net (code "143") (name "unconnected-(U1-PE1-Pad142)") (class "Default")
      (node (ref "U1") (pin "142") (pinfunction "PE1_142") (pintype "passive"))
    )
    (net (code "144") (name "unconnected-(U1-PE2-Pad1)") (class "Default")
      (node (ref "U1") (pin "1") (pinfunction "PE2_1") (pintype "passive"))
    )
    (net (code "145") (name "unconnected-(U1-PE3-Pad2)") (class "Default")
      (node (ref "U1") (pin "2") (pinfunction "PE3_2") (pintype "passive"))
    )
    (net (code "146") (name "unconnected-(U1-PE4-Pad3)") (class "Default")
      (node (ref "U1") (pin "3") (pinfunction "PE4_3") (pintype "passive"))
    )
    (net (code "147") (name "unconnected-(U1-PE5-Pad4)") (class "Default")
      (node (ref "U1") (pin "4") (pinfunction "PE5_4") (pintype "passive"))
    )
    (net (code "148") (name "unconnected-(U1-PE6-Pad5)") (class "Default")
      (node (ref "U1") (pin "5") (pinfunction "PE6_5") (pintype "passive"))
    )
    (net (code "149") (name "unconnected-(U1-PE12-Pad65)") (class "Default")
      (node (ref "U1") (pin "65") (pinfunction "PE12_65") (pintype "passive"))
    )
    (net (code "150") (name "unconnected-(U1-PE13-Pad66)") (class "Default")
      (node (ref "U1") (pin "66") (pinfunction "PE13_66") (pintype "passive"))
    )
    (net (code "151") (name "unconnected-(U1-PE14-Pad67)") (class "Default")
      (node (ref "U1") (pin "67") (pinfunction "PE14_67") (pintype "passive"))
    )
    (net (code "152") (name "unconnected-(U1-PE15-Pad68)") (class "Default")
      (node (ref "U1") (pin "68") (pinfunction "PE15_68") (pintype "passive"))
    )
    (net (code "153") (name "unconnected-(U1-PF2-Pad12)") (class "Default")
      (node (ref "U1") (pin "12") (pinfunction "PF2_12") (pintype "passive"))
    )
    (net (code "154") (name "unconnected-(U1-PF3-Pad13)") (class "Default")
      (node (ref "U1") (pin "13") (pinfunction "PF3_13") (pintype "passive"))
    )
    (net (code "155") (name "unconnected-(U1-PF4-Pad14)") (class "Default")
      (node (ref "U1") (pin "14") (pinfunction "PF4_14") (pintype "passive"))
    )
    (net (code "156") (name "unconnected-(U1-PF5-Pad15)") (class "Default")
      (node (ref "U1") (pin "15") (pinfunction "PF5_15") (pintype "passive"))
    )
    (net (code "157") (name "unconnected-(U1-PF6-Pad18)") (class "Default")
      (node (ref "U1") (pin "18") (pinfunction "PF6_18") (pintype "passive"))
    )
    (net (code "158") (name "unconnected-(U1-PF7-Pad19)") (class "Default")
      (node (ref "U1") (pin "19") (pinfunction "PF7_19") (pintype "passive"))
    )
    (net (code "159") (name "unconnected-(U1-PF8-Pad20)") (class "Default")
      (node (ref "U1") (pin "20") (pinfunction "PF8_20") (pintype "passive"))
    )
    (net (code "160") (name "unconnected-(U1-PF9-Pad21)") (class "Default")
      (node (ref "U1") (pin "21") (pinfunction "PF9_21") (pintype "passive"))
    )
    (net (code "161") (name "unconnected-(U1-PF10-Pad22)") (class "Default")
      (node (ref "U1") (pin "22") (pinfunction "PF10_22") (pintype "passive"))
    )
    (net (code "162") (name "unconnected-(U1-PG2-Pad87)") (class "Default")
      (node (ref "U1") (pin "87") (pinfunction "PG2_87") (pintype "passive"))
    )
    (net (code "163") (name "unconnected-(U1-PG3-Pad88)") (class "Default")
      (node (ref "U1") (pin "88") (pinfunction "PG3_88") (pintype "passive"))
    )
    (net (code "164") (name "unconnected-(U1-PG4-Pad89)") (class "Default")
      (node (ref "U1") (pin "89") (pinfunction "PG4_89") (pintype "passive"))
    )
    (net (code "165") (name "unconnected-(U1-PG5-Pad90)") (class "Default")
      (node (ref "U1") (pin "90") (pinfunction "PG5_90") (pintype "passive"))
    )
    (net (code "166") (name "unconnected-(U1-PG6-Pad91)") (class "Default")
      (node (ref "U1") (pin "91") (pinfunction "PG6_91") (pintype "passive"))
    )
    (net (code "167") (name "unconnected-(U1-PG7-Pad92)") (class "Default")
      (node (ref "U1") (pin "92") (pinfunction "PG7_92") (pintype "passive"))
    )
    (net (code "168") (name "unconnected-(U1-PG8-Pad93)") (class "Default")
      (node (ref "U1") (pin "93") (pinfunction "PG8_93") (pintype "passive"))
    )
    (net (code "169") (name "unconnected-(U1-PG9-Pad124)") (class "Default")
      (node (ref "U1") (pin "124") (pinfunction "PG9_124") (pintype "passive"))
    )
    (net (code "170") (name "unconnected-(U1-PG10-Pad125)") (class "Default")
      (node (ref "U1") (pin "125") (pinfunction "PG10_125") (pintype "passive"))
    )
    (net (code "171") (name "unconnected-(U1-PG11-Pad126)") (class "Default")
      (node (ref "U1") (pin "126") (pinfunction "PG11_126") (pintype "passive"))
    )
    (net (code "172") (name "unconnected-(U1-PG12-Pad127)") (class "Default")
      (node (ref "U1") (pin "127") (pinfunction "PG12_127") (pintype "passive"))
    )
    (net (code "173") (name "unconnected-(U1-PG13-Pad128)") (class "Default")
      (node (ref "U1") (pin "128") (pinfunction "PG13_128") (pintype "passive"))
    )
    (net (code "174") (name "unconnected-(U1-PG14-Pad129)") (class "Default")
      (node (ref "U1") (pin "129") (pinfunction "PG14_129") (pintype "passive"))
    )
    (net (code "175") (name "unconnected-(U1-VREF+-Pad32)") (class "Default")
      (node (ref "U1") (pin "32") (pinfunction "VREF+_32") (pintype "passive"))
    )
    (net (code "176") (name "unconnected-(U1-VSSA-Pad31)") (class "Default")
      (node (ref "U1") (pin "31") (pinfunction "VSSA_31") (pintype "passive"))
    )
    (net (code "177") (name "unconnected-(U3-EP-Pad25)") (class "Default")
      (node (ref "U3") (pin "25") (pinfunction "EP_25") (pintype "passive"))
    )
    (net (code "178") (name "unconnected-(U3-NC-Pad2)") (class "Default")
      (node (ref "U3") (pin "2") (pinfunction "NC_2") (pintype "passive"))
    )
    (net (code "179") (name "unconnected-(U3-NC-Pad3)") (class "Default")
      (node (ref "U3") (pin "3") (pinfunction "NC_3") (pintype "passive"))
    )
    (net (code "180") (name "unconnected-(U3-NC-Pad4)") (class "Default")
      (node (ref "U3") (pin "4") (pinfunction "NC_4") (pintype "passive"))
    )
    (net (code "181") (name "unconnected-(U3-NC-Pad5)") (class "Default")
      (node (ref "U3") (pin "5") (pinfunction "NC_5") (pintype "passive"))
    )
    (net (code "182") (name "unconnected-(U3-NC-Pad6)") (class "Default")
      (node (ref "U3") (pin "6") (pinfunction "NC_6") (pintype "passive"))
    )
    (net (code "183") (name "unconnected-(U3-NC-Pad14)") (class "Default")
      (node (ref "U3") (pin "14") (pinfunction "NC_14") (pintype "passive"))
    )
    (net (code "184") (name "unconnected-(U3-NC-Pad15)") (class "Default")
      (node (ref "U3") (pin "15") (pinfunction "NC_15") (pintype "passive"))
    )
    (net (code "185") (name "unconnected-(U3-NC-Pad16)") (class "Default")
      (node (ref "U3") (pin "16") (pinfunction "NC_16") (pintype "passive"))
    )
    (net (code "186") (name "unconnected-(U3-NC-Pad17)") (class "Default")
      (node (ref "U3") (pin "17") (pinfunction "NC_17") (pintype "passive"))
    )
    (net (code "187") (name "unconnected-(U3-RESV-Pad19)") (class "Default")
      (node (ref "U3") (pin "19") (pinfunction "RESV_19") (pintype "passive"))
    )
    (net (code "188") (name "unconnected-(U21-SBU1-PadA8)") (class "Default")
      (node (ref "U21") (pin "A8") (pinfunction "SBU1_A8") (pintype "passive"))
    )
    (net (code "189") (name "unconnected-(U21-SBU2-PadB8)") (class "Default")
      (node (ref "U21") (pin "B8") (pinfunction "SBU2_B8") (pintype "passive"))
    )
    (net (code "190") (name "unconnected-(U22-SBU1-PadA8)") (class "Default")
      (node (ref "U22") (pin "A8") (pinfunction "SBU1_A8") (pintype "passive"))
    )
    (net (code "191") (name "unconnected-(U22-SBU2-PadB8)") (class "Default")
      (node (ref "U22") (pin "B8") (pinfunction "SBU2_B8") (pintype "passive"))
    )
    (net (code "192") (name "unconnected-(U24-Pad1)") (class "Default")
      (node (ref "U24") (pin "1") (pinfunction "1_1") (pintype "passive"))
    )
    (net (code "193") (name "unconnected-(U24-Pad4)") (class "Default")
      (node (ref "U24") (pin "4") (pinfunction "4_4") (pintype "passive"))
    )
    (net (code "194") (name "unconnected-(U25-PWRJ-Pad25)") (class "Default")
      (node (ref "U25") (pin "25") (pinfunction "PWRJ_25") (pintype "passive"))
    )
    (net (code "195") (name "unconnected-(U25-TESTJ-Pad27)") (class "Default")
      (node (ref "U25") (pin "27") (pinfunction "TESTJ_27") (pintype "passive"))
    )
    (net (code "196") (name "unconnected-(U26-Pad1)") (class "Default")
      (node (ref "U26") (pin "1") (pinfunction "1_1") (pintype "passive"))
    )
    (net (code "197") (name "unconnected-(U26-Pad4)") (class "Default")
      (node (ref "U26") (pin "4") (pinfunction "4_4") (pintype "passive"))
    )
    (net (code "198") (name "unconnected-(U27-Pad1)") (class "Default")
      (node (ref "U27") (pin "1") (pinfunction "1_1") (pintype "passive"))
    )
    (net (code "199") (name "unconnected-(U27-Pad4)") (class "Default")
      (node (ref "U27") (pin "4") (pinfunction "4_4") (pintype "passive"))
    )
    (net (code "200") (name "unconnected-(U32-IO5-Pad29)") (class "Default")
      (node (ref "U32") (pin "29") (pinfunction "IO5_29") (pintype "passive"))
    )
    (net (code "201") (name "unconnected-(U32-IO12-Pad14)") (class "Default")
      (node (ref "U32") (pin "14") (pinfunction "IO12_14") (pintype "passive"))
    )
    (net (code "202") (name "unconnected-(U32-IO13-Pad16)") (class "Default")
      (node (ref "U32") (pin "16") (pinfunction "IO13_16") (pintype "passive"))
    )
    (net (code "203") (name "unconnected-(U32-IO14-Pad13)") (class "Default")
      (node (ref "U32") (pin "13") (pinfunction "IO14_13") (pintype "passive"))
    )
    (net (code "204") (name "unconnected-(U32-IO15-Pad23)") (class "Default")
      (node (ref "U32") (pin "23") (pinfunction "IO15_23") (pintype "passive"))
    )
    (net (code "205") (name "unconnected-(U32-IO16-Pad27)") (class "Default")
      (node (ref "U32") (pin "27") (pinfunction "IO16_27") (pintype "passive"))
    )
    (net (code "206") (name "unconnected-(U32-IO17-Pad28)") (class "Default")
      (node (ref "U32") (pin "28") (pinfunction "IO17_28") (pintype "passive"))
    )
    (net (code "207") (name "unconnected-(U32-IO18-Pad30)") (class "Default")
      (node (ref "U32") (pin "30") (pinfunction "IO18_30") (pintype "passive"))
    )
    (net (code "208") (name "unconnected-(U32-IO19-Pad31)") (class "Default")
      (node (ref "U32") (pin "31") (pinfunction "IO19_31") (pintype "passive"))
    )
    (net (code "209") (name "unconnected-(U32-IO23-Pad37)") (class "Default")
      (node (ref "U32") (pin "37") (pinfunction "IO23_37") (pintype "passive"))
    )
    (net (code "210") (name "unconnected-(U32-IO25-Pad10)") (class "Default")
      (node (ref "U32") (pin "10") (pinfunction "IO25_10") (pintype "passive"))
    )
    (net (code "211") (name "unconnected-(U32-IO26-Pad11)") (class "Default")
      (node (ref "U32") (pin "11") (pinfunction "IO26_11") (pintype "passive"))
    )
    (net (code "212") (name "unconnected-(U32-IO27-Pad12)") (class "Default")
      (node (ref "U32") (pin "12") (pinfunction "IO27_12") (pintype "passive"))
    )
    (net (code "213") (name "unconnected-(U32-IO32-Pad8)") (class "Default")
      (node (ref "U32") (pin "8") (pinfunction "IO32_8") (pintype "passive"))
    )
    (net (code "214") (name "unconnected-(U32-IO33-Pad9)") (class "Default")
      (node (ref "U32") (pin "9") (pinfunction "IO33_9") (pintype "passive"))
    )
    (net (code "215") (name "unconnected-(U32-NC-Pad32)") (class "Default")
      (node (ref "U32") (pin "32") (pinfunction "NC_32") (pintype "passive"))
    )
    (net (code "216") (name "unconnected-(U32-SCK{slash}CLK-Pad20)") (class "Default")
      (node (ref "U32") (pin "20") (pinfunction "SCK/CLK_20") (pintype "passive"))
    )
    (net (code "217") (name "unconnected-(U32-SCS{slash}CMD-Pad19)") (class "Default")
      (node (ref "U32") (pin "19") (pinfunction "SCS/CMD_19") (pintype "passive"))
    )
    (net (code "218") (name "unconnected-(U32-SDI{slash}SD1-Pad22)") (class "Default")
      (node (ref "U32") (pin "22") (pinfunction "SDI/SD1_22") (pintype "passive"))
    )
    (net (code "219") (name "unconnected-(U32-SDO{slash}SD0-Pad21)") (class "Default")
      (node (ref "U32") (pin "21") (pinfunction "SDO/SD0_21") (pintype "passive"))
    )
    (net (code "220") (name "unconnected-(U32-SENSOR_VN-Pad5)") (class "Default")
      (node (ref "U32") (pin "5") (pinfunction "SENSOR_VN_5") (pintype "passive"))
    )
    (net (code "221") (name "unconnected-(U32-SENSOR_VP-Pad4)") (class "Default")
      (node (ref "U32") (pin "4") (pinfunction "SENSOR_VP_4") (pintype "passive"))
    )
    (net (code "222") (name "unconnected-(U32-SHD{slash}SD2-Pad17)") (class "Default")
      (node (ref "U32") (pin "17") (pinfunction "SHD/SD2_17") (pintype "passive"))
    )
    (net (code "223") (name "unconnected-(U32-SWP{slash}SD3-Pad18)") (class "Default")
      (node (ref "U32") (pin "18") (pinfunction "SWP/SD3_18") (pintype "passive"))
    )
    (net (code "224") (name "unconnected-(U37-CHR0-Pad15)") (class "Default")
      (node (ref "U37") (pin "15") (pinfunction "CHR0_15") (pintype "passive"))
    )
    (net (code "225") (name "unconnected-(U37-CHR1-Pad14)") (class "Default")
      (node (ref "U37") (pin "14") (pinfunction "CHR1_14") (pintype "passive"))
    )
    (net (code "226") (name "unconnected-(U37-CHREN-Pad13)") (class "Default")
      (node (ref "U37") (pin "13") (pinfunction "CHREN_13") (pintype "passive"))
    )
    (net (code "227") (name "unconnected-(U37-CTS-Pad23)") (class "Default")
      (node (ref "U37") (pin "23") (pinfunction "CTS_23") (pintype "passive"))
    )
    (net (code "228") (name "unconnected-(U37-DCD-Pad1)") (class "Default")
      (node (ref "U37") (pin "1") (pinfunction "DCD_1") (pintype "passive"))
    )
    (net (code "229") (name "unconnected-(U37-DSR-Pad27)") (class "Default")
      (node (ref "U37") (pin "27") (pinfunction "DSR_27") (pintype "passive"))
    )
    (net (code "230") (name "unconnected-(U37-GPIO.0{slash}TXT-Pad19)") (class "Default")
      (node (ref "U37") (pin "19") (pinfunction "GPIO.0/TXT_19") (pintype "passive"))
    )
    (net (code "231") (name "unconnected-(U37-GPIO.1{slash}RXT-Pad18)") (class "Default")
      (node (ref "U37") (pin "18") (pinfunction "GPIO.1/RXT_18") (pintype "passive"))
    )
    (net (code "232") (name "unconnected-(U37-GPIO.2{slash}RS485-Pad17)") (class "Default")
      (node (ref "U37") (pin "17") (pinfunction "GPIO.2/RS485_17") (pintype "passive"))
    )
    (net (code "233") (name "unconnected-(U37-GPIO.3{slash}WAKEUP-Pad16)") (class "Default")
      (node (ref "U37") (pin "16") (pinfunction "GPIO.3/WAKEUP_16") (pintype "passive"))
    )
    (net (code "234") (name "unconnected-(U37-GPIO.4-Pad22)") (class "Default")
      (node (ref "U37") (pin "22") (pinfunction "GPIO.4_22") (pintype "passive"))
    )
    (net (code "235") (name "unconnected-(U37-GPIO.5-Pad21)") (class "Default")
      (node (ref "U37") (pin "21") (pinfunction "GPIO.5_21") (pintype "passive"))
    )
    (net (code "236") (name "unconnected-(U37-GPIO.6-Pad20)") (class "Default")
      (node (ref "U37") (pin "20") (pinfunction "GPIO.6_20") (pintype "passive"))
    )
    (net (code "237") (name "unconnected-(U37-NC-Pad10)") (class "Default")
      (node (ref "U37") (pin "10") (pinfunction "NC_10") (pintype "passive"))
    )
    (net (code "238") (name "unconnected-(U37-RI{slash}CLK-Pad2)") (class "Default")
      (node (ref "U37") (pin "2") (pinfunction "RI/CLK_2") (pintype "passive"))
    )
    (net (code "239") (name "unconnected-(U37-RTS-Pad24)") (class "Default")
      (node (ref "U37") (pin "24") (pinfunction "RTS_24") (pintype "passive"))
    )
    (net (code "240") (name "unconnected-(U37-SUSPEND-Pad12)") (class "Default")
      (node (ref "U37") (pin "12") (pinfunction "SUSPEND_12") (pintype "passive"))
    )
    (net (code "241") (name "unconnected-(U37-SUSPENDb-Pad11)") (class "Default")
      (node (ref "U37") (pin "11") (pinfunction "SUSPENDb_11") (pintype "passive"))
    )
  )
)
